# MOMO_2019.net
KiCad netlist of a schematic drawn in EAGLE
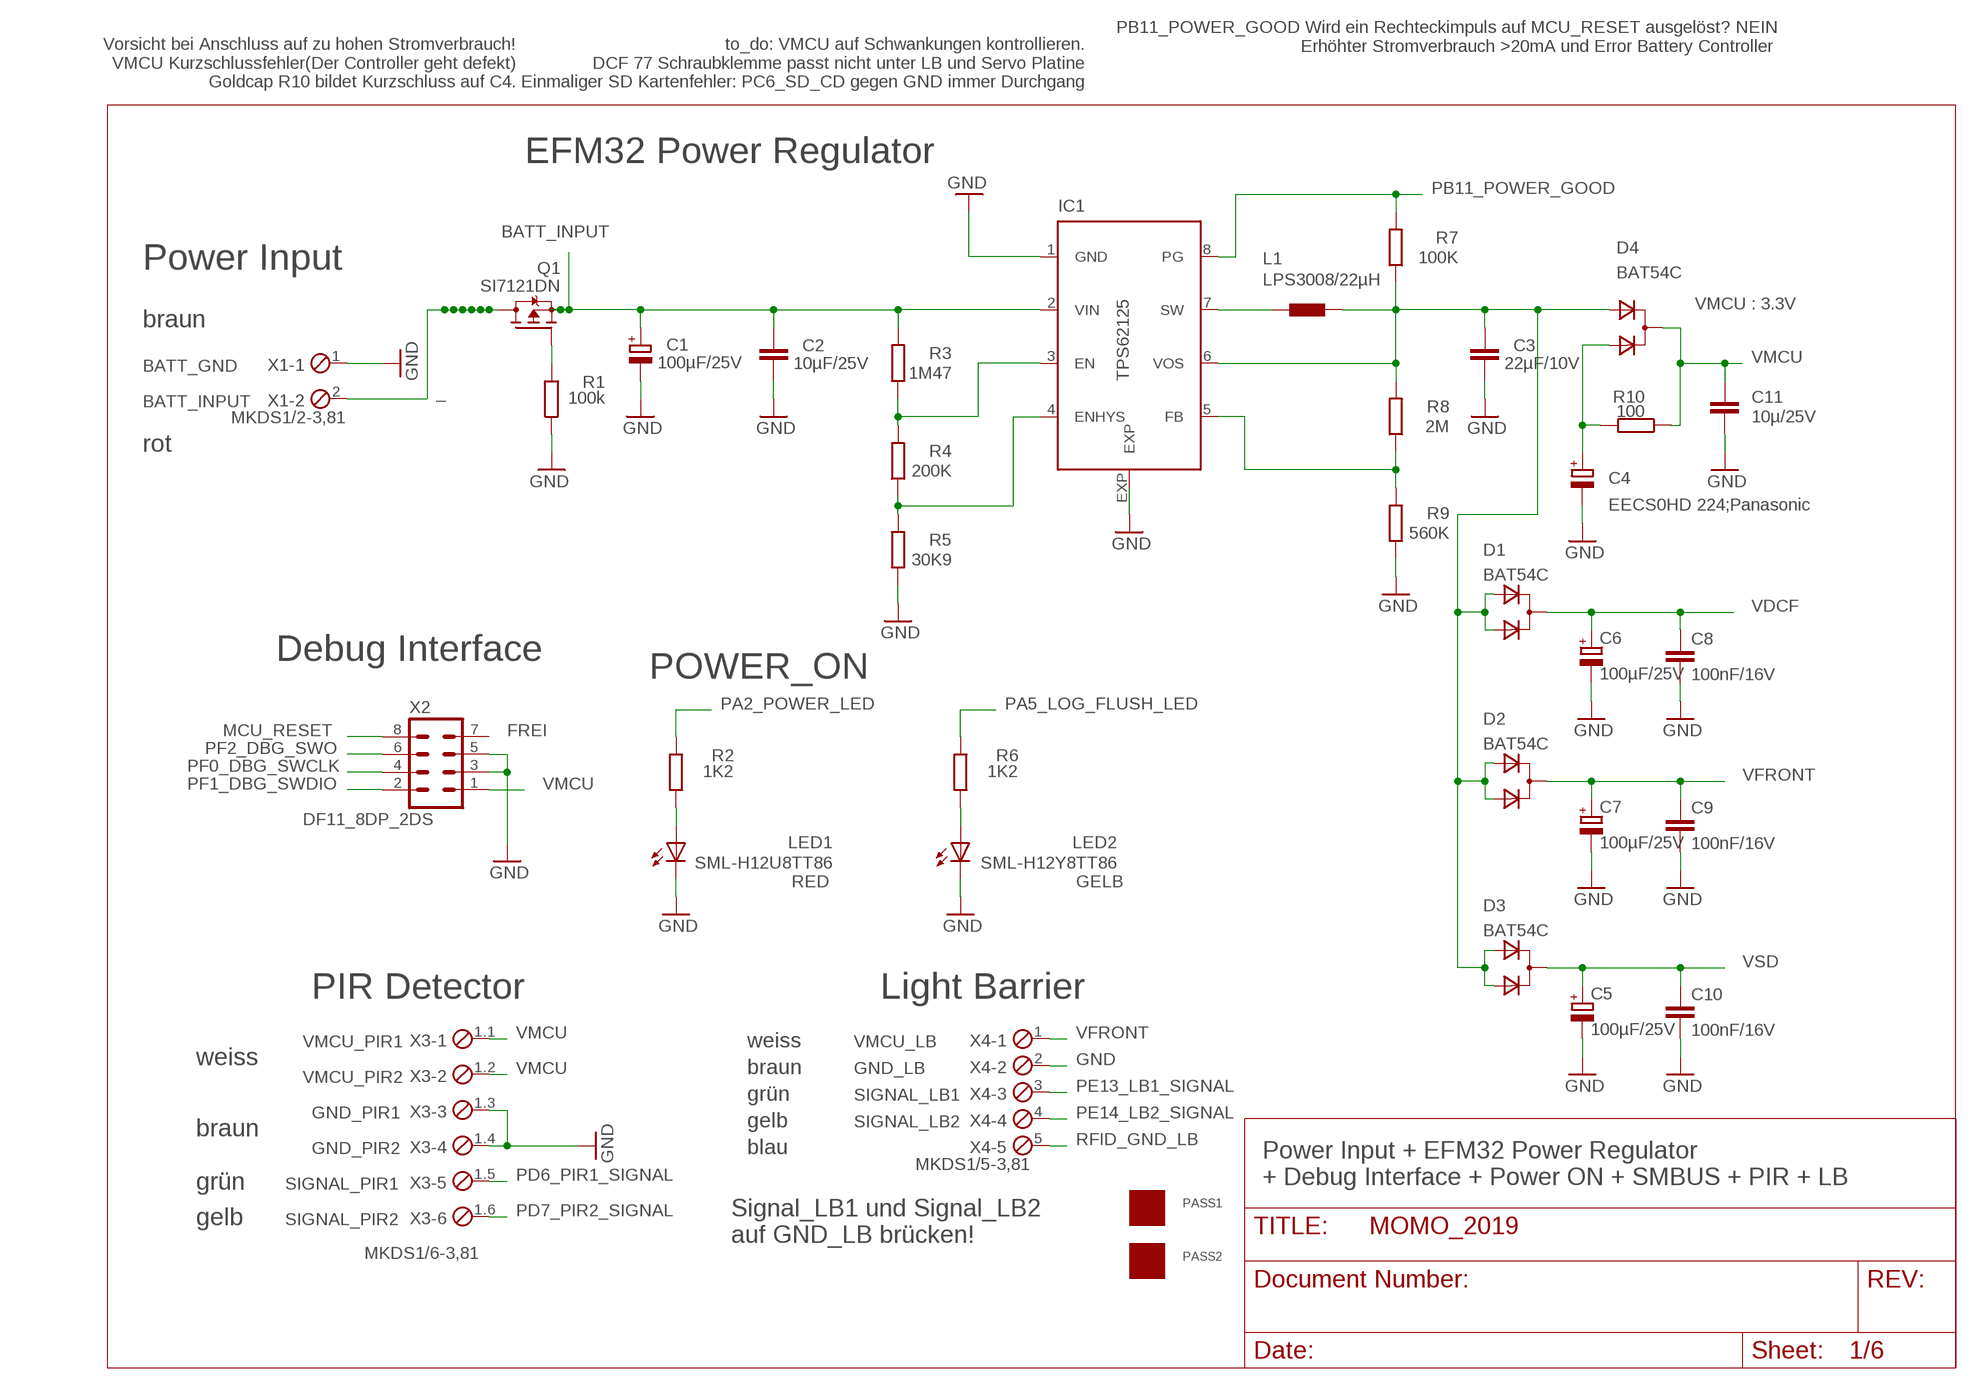
[diagram p0: schematic, sheet 1]
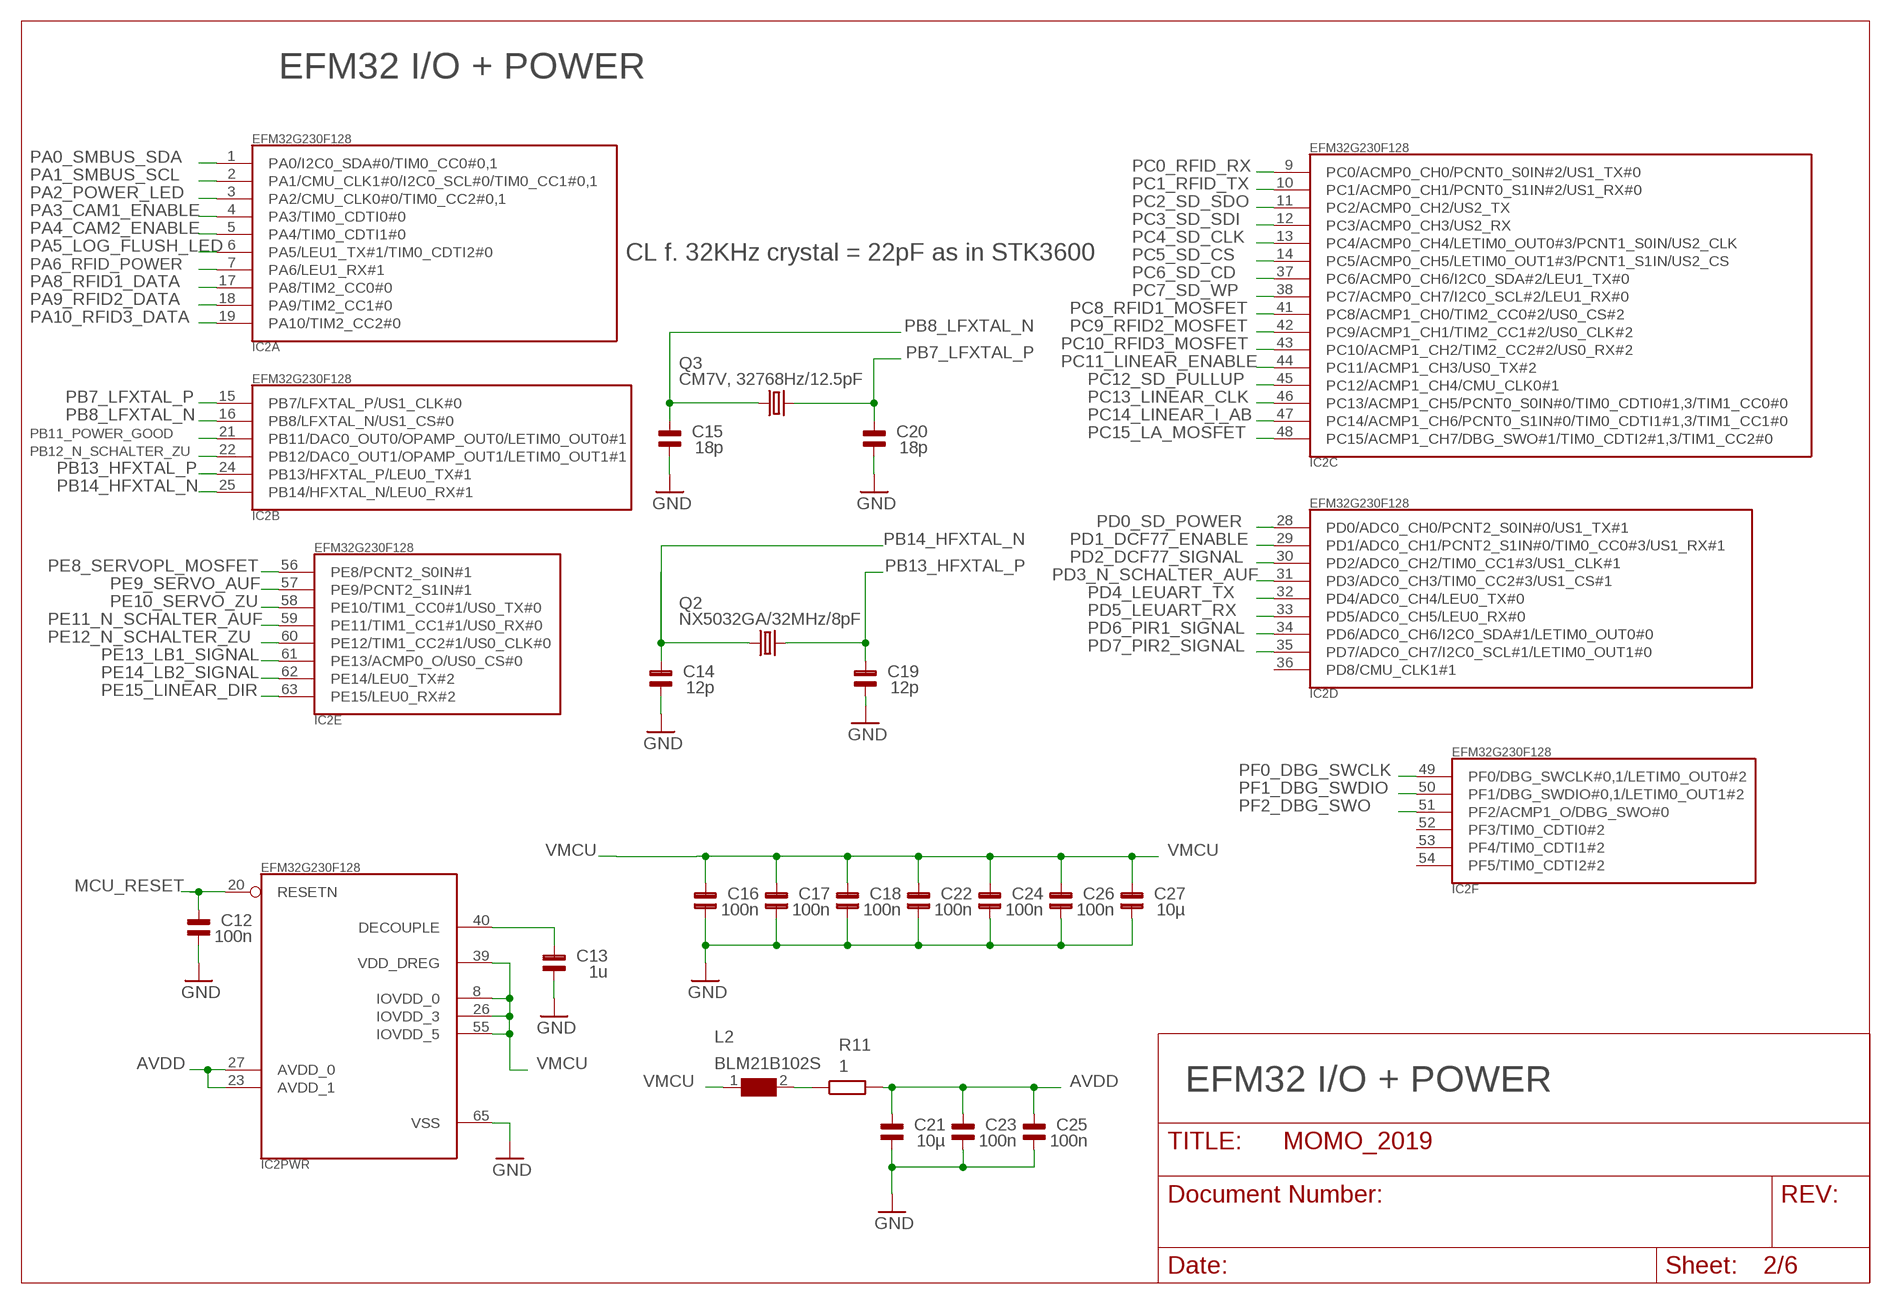
[diagram p1: schematic, sheet 2]
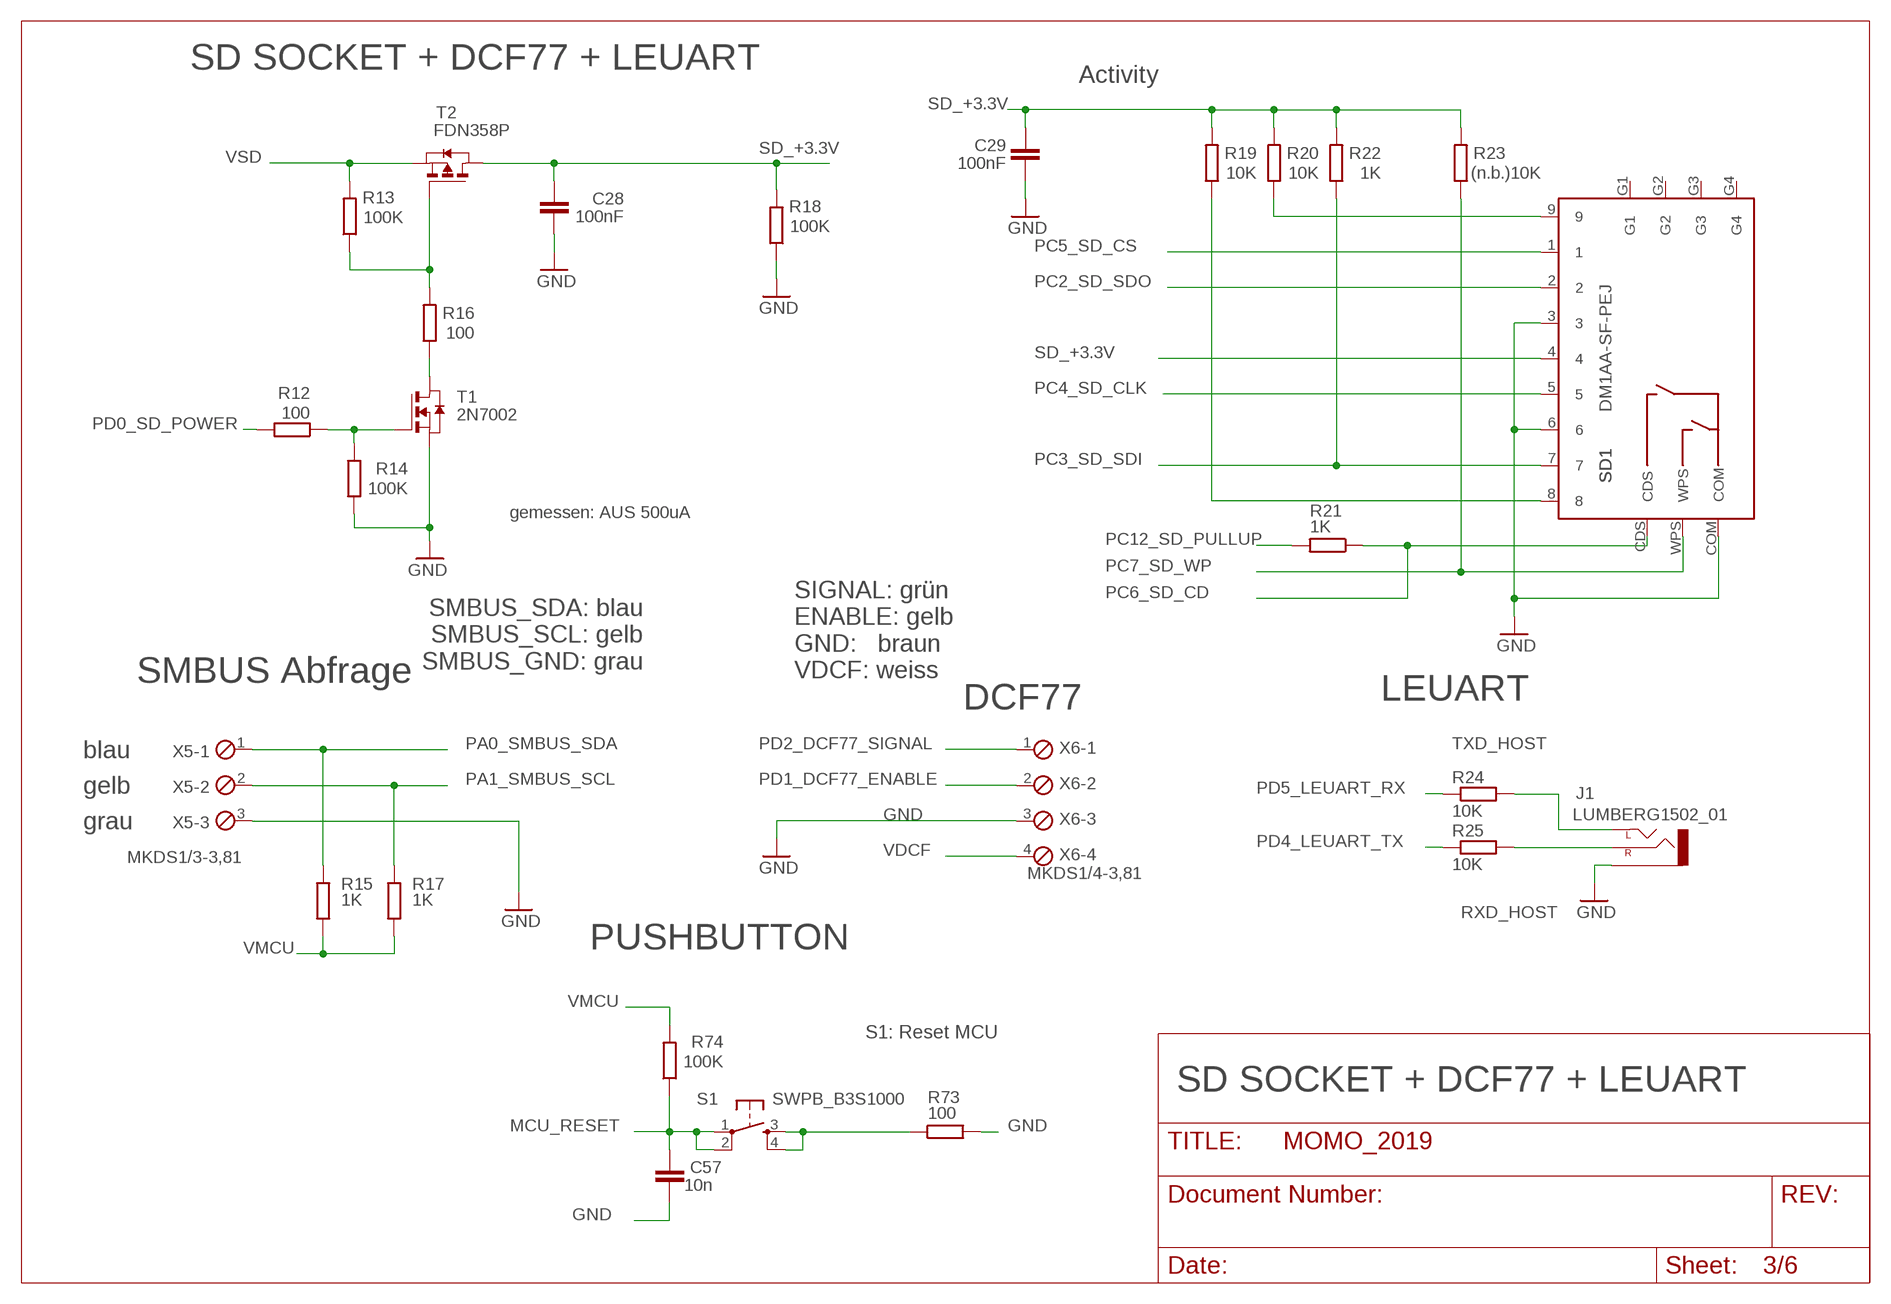
[diagram p2: schematic, sheet 3]
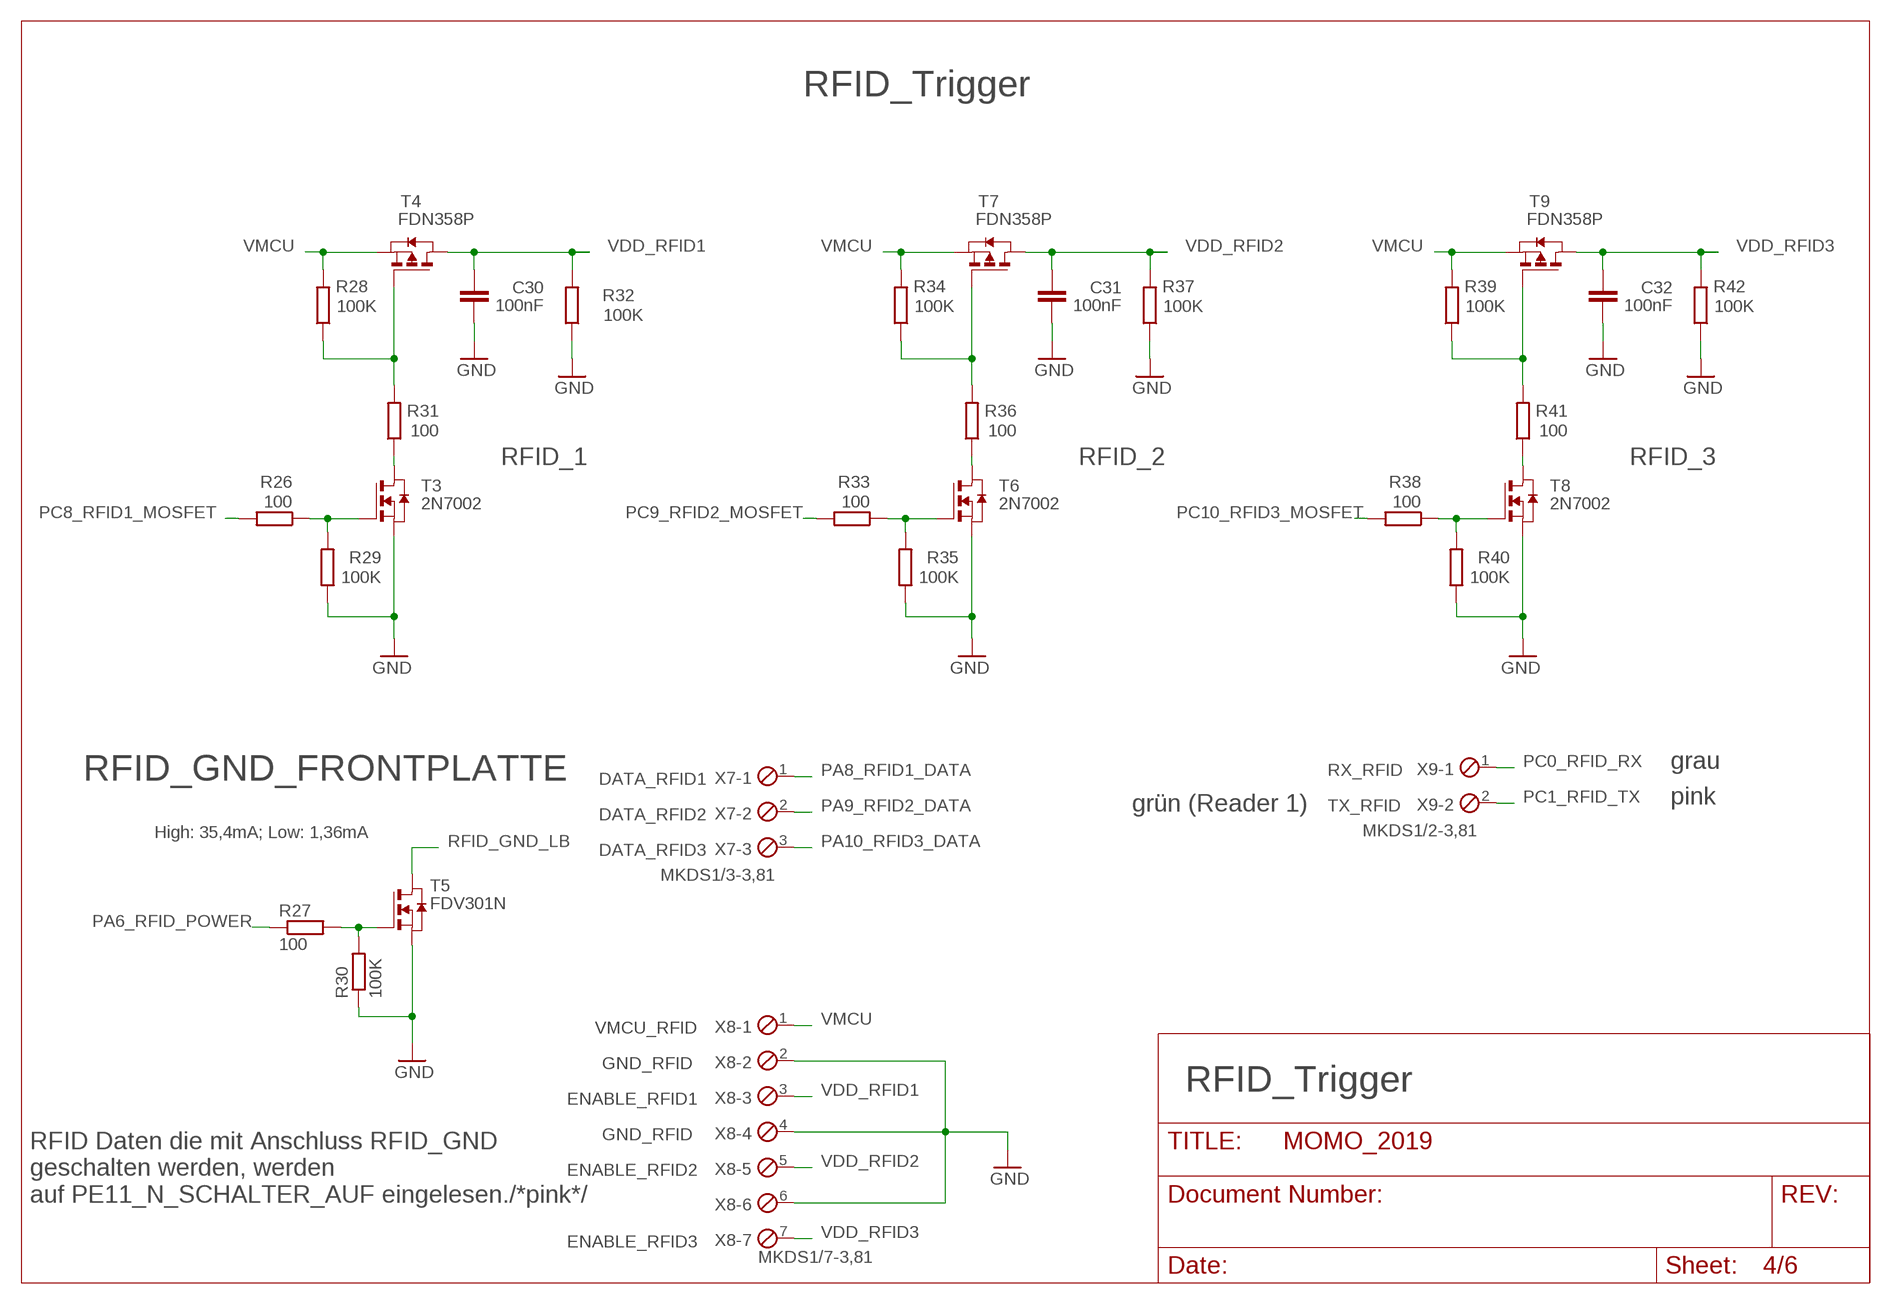
[diagram p3: schematic, sheet 4]
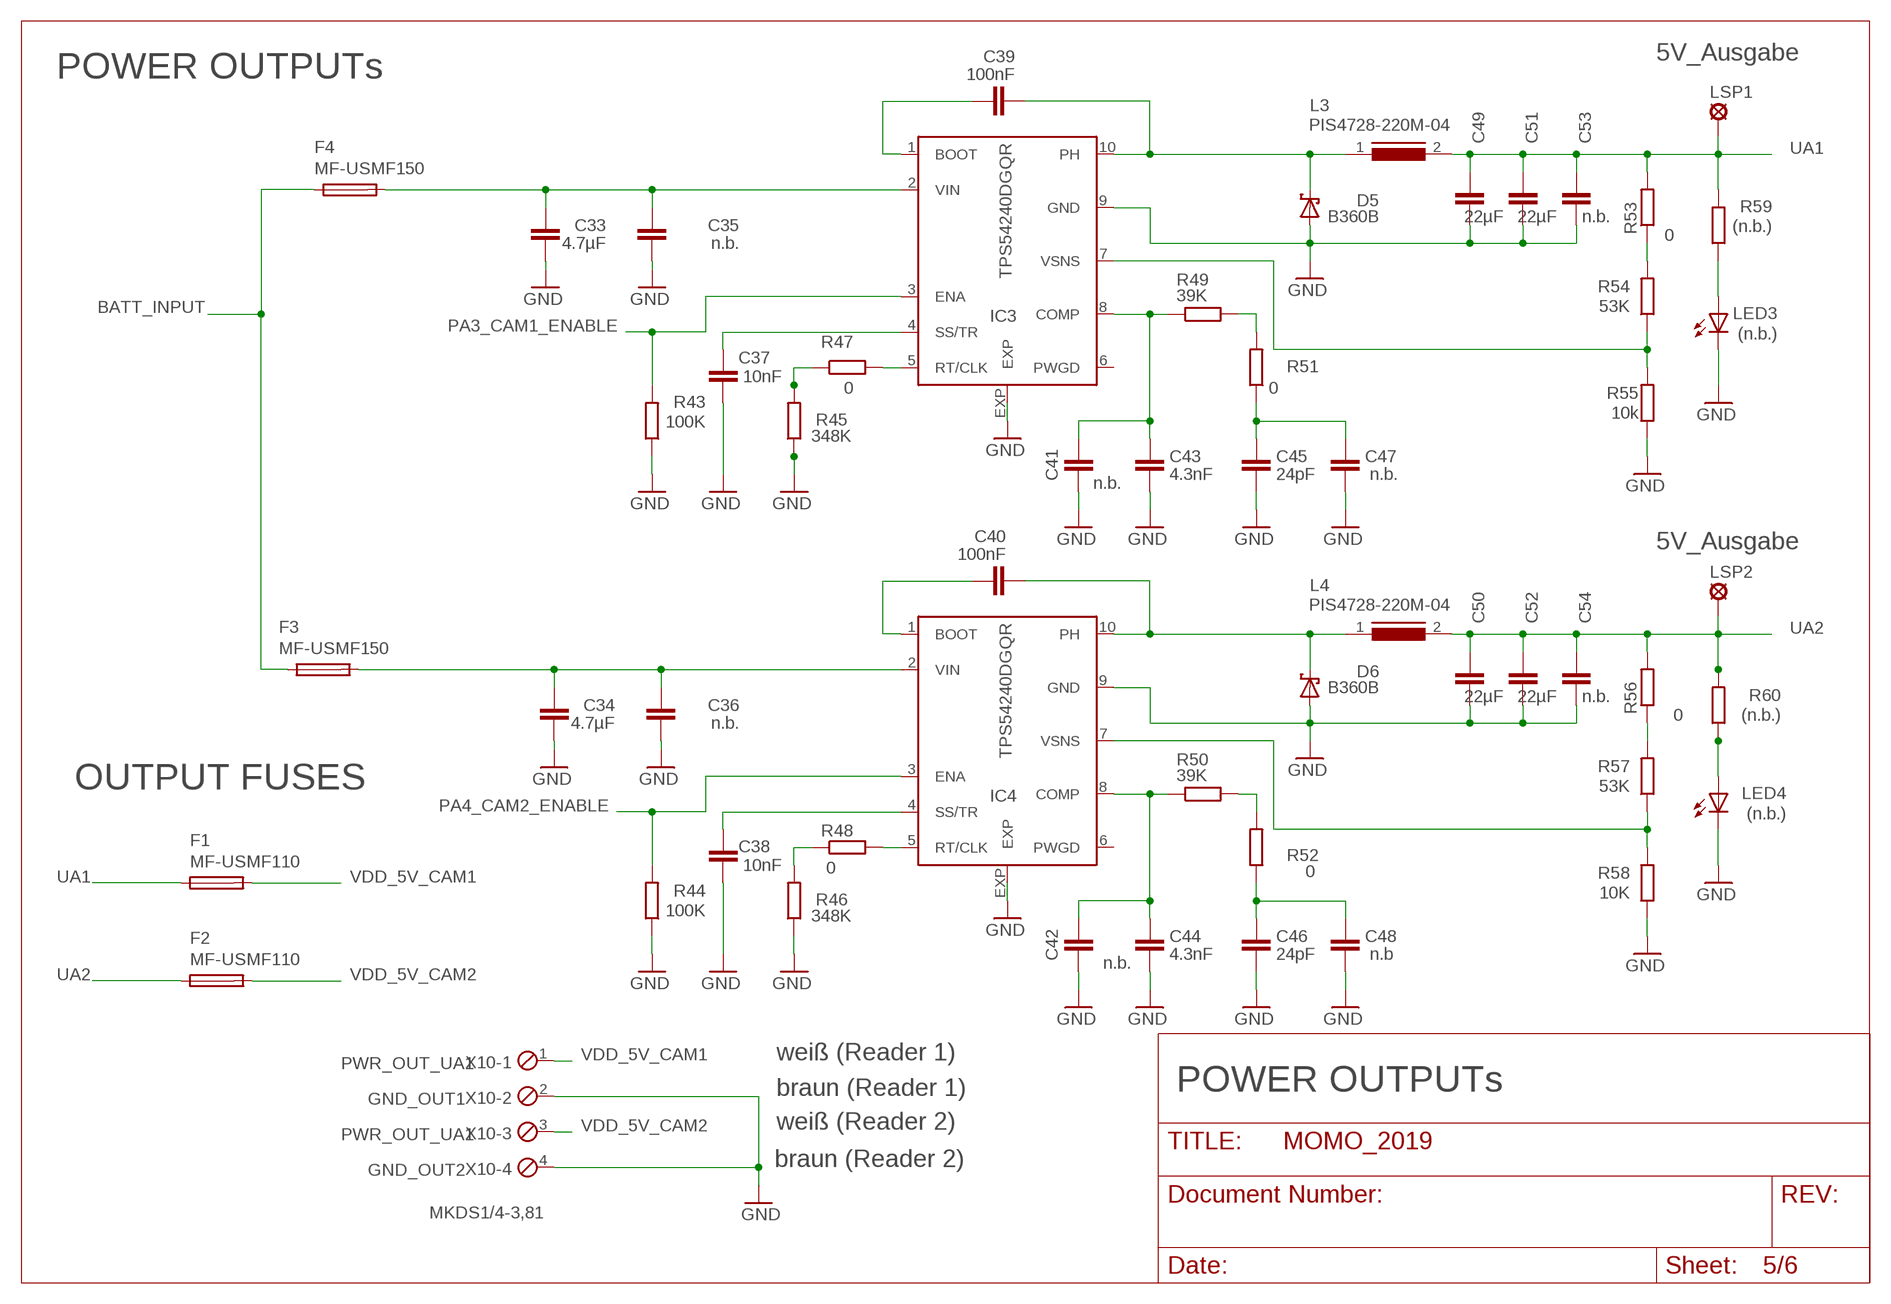
[diagram p4: schematic, sheet 5]
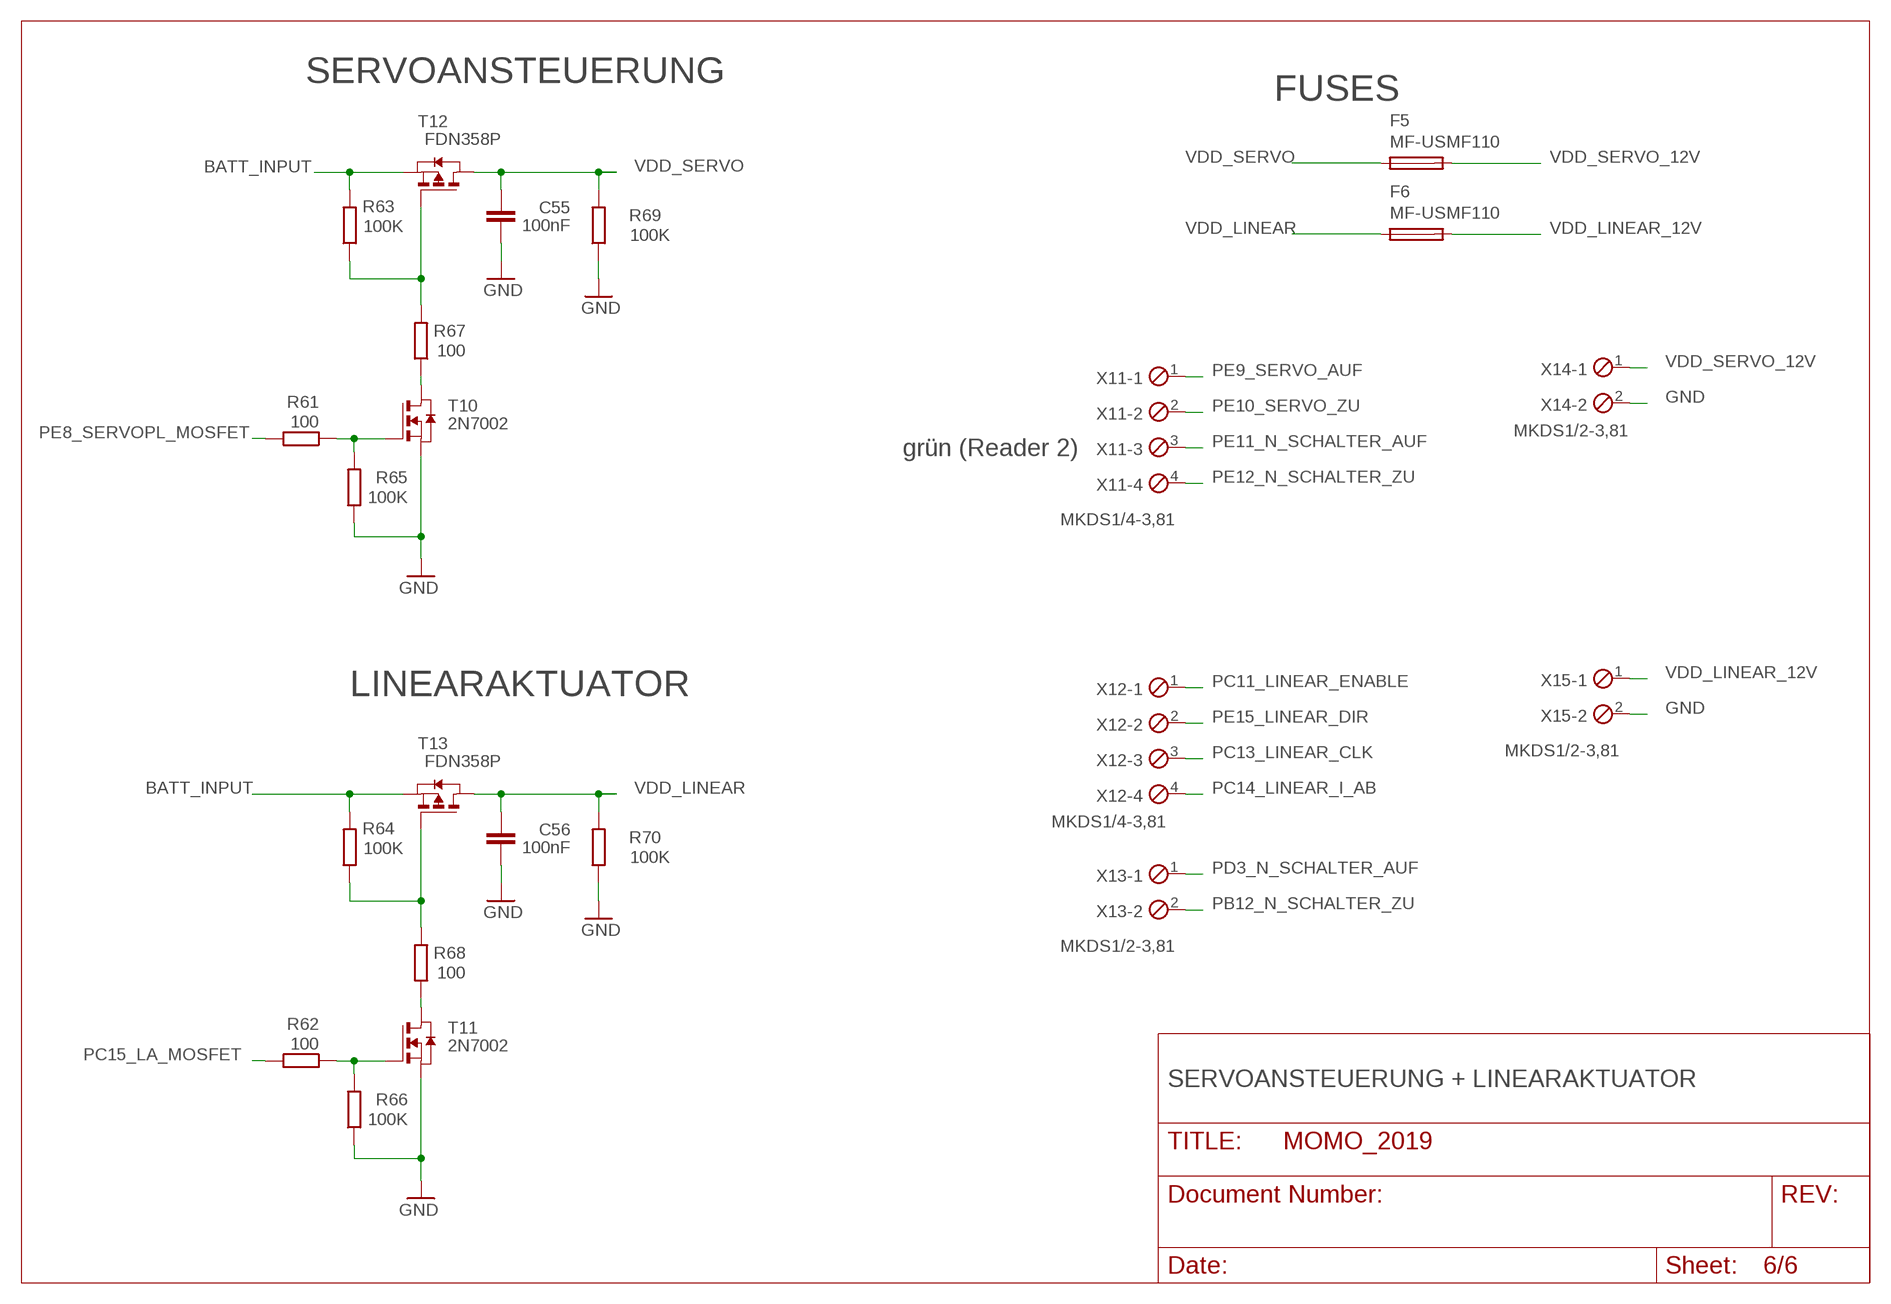
[diagram p5: schematic, sheet 6]

(export (version "E")
  (design (tool "Eeschema 10.0.6"))
  (components
    (comp (ref "C1")
      (value "100µF/25V")
      (footprint "eagle-import:PANASONIC_E")
      (libsource (lib "eagle-import") (part "CPOL-EUE"))
    )
    (comp (ref "C2")
      (value "10µF/25V")
      (footprint "eagle-import:C1206")
      (libsource (lib "eagle-import") (part "C-EUC1206"))
    )
    (comp (ref "C3")
      (value "22µF/10V")
      (footprint "eagle-import:C0603")
      (libsource (lib "eagle-import") (part "C-EUC0603"))
    )
    (comp (ref "C4")
      (value "EECS0HD 224;Panasonic")
      (footprint "eagle-import:GOLDCAPSPK-V")
      (libsource (lib "eagle-import") (part "GOLDCAPSPK-V"))
    )
    (comp (ref "C5")
      (value "100µF/25V")
      (footprint "eagle-import:PANASONIC_E")
      (libsource (lib "eagle-import") (part "CPOL-EUE"))
    )
    (comp (ref "C6")
      (value "100µF/25V")
      (footprint "eagle-import:PANASONIC_E")
      (libsource (lib "eagle-import") (part "CPOL-EUE"))
    )
    (comp (ref "C7")
      (value "100µF/25V")
      (footprint "eagle-import:PANASONIC_E")
      (libsource (lib "eagle-import") (part "CPOL-EUE"))
    )
    (comp (ref "C8")
      (value "100nF/16V")
      (footprint "eagle-import:C0805")
      (libsource (lib "eagle-import") (part "C-EUC0805"))
    )
    (comp (ref "C9")
      (value "100nF/16V")
      (footprint "eagle-import:C0805")
      (libsource (lib "eagle-import") (part "C-EUC0805"))
    )
    (comp (ref "C10")
      (value "100nF/16V")
      (footprint "eagle-import:C0805")
      (libsource (lib "eagle-import") (part "C-EUC0805"))
    )
    (comp (ref "C11")
      (value "10µ/25V")
      (footprint "eagle-import:C1206")
      (libsource (lib "eagle-import") (part "C-EUC1206"))
    )
    (comp (ref "D1")
      (value "BAT54C")
      (footprint "eagle-import:SOT-23$1")
      (libsource (lib "eagle-import") (part "D2A_SOT23"))
    )
    (comp (ref "D2")
      (value "BAT54C")
      (footprint "eagle-import:SOT-23$1")
      (libsource (lib "eagle-import") (part "D2A_SOT23"))
    )
    (comp (ref "D3")
      (value "BAT54C")
      (footprint "eagle-import:SOT-23$1")
      (libsource (lib "eagle-import") (part "D2A_SOT23"))
    )
    (comp (ref "D4")
      (value "BAT54C")
      (footprint "eagle-import:SOT-23$1")
      (libsource (lib "eagle-import") (part "D2A_SOT23"))
    )
    (comp (ref "IC1")
      (value "TPS62125")
      (footprint "eagle-import:DSG_PWSO-N8_EXP")
      (libsource (lib "eagle-import") (part "TPS62125"))
    )
    (comp (ref "L1")
      (value "LPS3008/22µH")
      (footprint "eagle-import:LPS3008")
      (libsource (lib "eagle-import") (part "LPS3008"))
    )
    (comp (ref "LED1")
      (value "SML-H12U8TT86")
      (footprint "eagle-import:CHIPLED_0805")
      (libsource (lib "eagle-import") (part "LEDCHIPLED_0805"))
    )
    (comp (ref "LED2")
      (value "SML-H12Y8TT86")
      (footprint "eagle-import:CHIPLED_0805")
      (libsource (lib "eagle-import") (part "LEDCHIPLED_0805"))
    )
    (comp (ref "PASS1")
      (value "ROUND_1MM1.5")
      (footprint "eagle-import:ROUND2_1.5MM")
      (libsource (lib "eagle-import") (part "ROUND_1MM1.5"))
    )
    (comp (ref "PASS2")
      (value "ROUND_1MM1.5")
      (footprint "eagle-import:ROUND2_1.5MM")
      (libsource (lib "eagle-import") (part "ROUND_1MM1.5"))
    )
    (comp (ref "Q1")
      (value "SI7121DN")
      (footprint "eagle-import:TRANSISTOR-FET_1212-8S")
      (libsource (lib "eagle-import") (part "TRANSISTOR-FET_SI7113DN"))
    )
    (comp (ref "R1")
      (value "100k")
      (footprint "eagle-import:R0805")
      (libsource (lib "eagle-import") (part "resistor_R-EU_R0805"))
    )
    (comp (ref "R2")
      (value "1K2")
      (footprint "eagle-import:R0805")
      (libsource (lib "eagle-import") (part "resistor_R-EU_R0805"))
    )
    (comp (ref "R3")
      (value "1M47")
      (footprint "eagle-import:R0805")
      (libsource (lib "eagle-import") (part "R-EU_R0805"))
    )
    (comp (ref "R4")
      (value "200K")
      (footprint "eagle-import:R0805")
      (libsource (lib "eagle-import") (part "R-EU_R0805"))
    )
    (comp (ref "R5")
      (value "30K9")
      (footprint "eagle-import:R0805")
      (libsource (lib "eagle-import") (part "R-EU_R0805"))
    )
    (comp (ref "R6")
      (value "1K2")
      (footprint "eagle-import:R0805")
      (libsource (lib "eagle-import") (part "resistor_R-EU_R0805"))
    )
    (comp (ref "R7")
      (value "100K")
      (footprint "eagle-import:R0805")
      (libsource (lib "eagle-import") (part "R-EU_R0805"))
    )
    (comp (ref "R8")
      (value "2M")
      (footprint "eagle-import:R0805")
      (libsource (lib "eagle-import") (part "R-EU_R0805"))
    )
    (comp (ref "R9")
      (value "560K")
      (footprint "eagle-import:R0805")
      (libsource (lib "eagle-import") (part "R-EU_R0805"))
    )
    (comp (ref "R10")
      (value "100")
      (footprint "eagle-import:R0805")
      (libsource (lib "eagle-import") (part "R-EU_R0805"))
    )
    (comp (ref "X1")
      (value "MKDS1/2-3,81")
      (footprint "eagle-import:2POL381")
      (libsource (lib "eagle-import") (part "MKDS1/2-3,81"))
    )
    (comp (ref "X2")
      (value "DF11_8DP_2DS")
      (footprint "eagle-import:DP11_8DP-2DS")
      (libsource (lib "eagle-import") (part "DP11_8DP_2DS"))
    )
    (comp (ref "X3")
      (value "MKDS1/6-3,81")
      (footprint "eagle-import:6POL381")
      (libsource (lib "eagle-import") (part "MKDS1/6-3,81"))
    )
    (comp (ref "X4")
      (value "MKDS1/5-3,81")
      (footprint "eagle-import:5POL381")
      (libsource (lib "eagle-import") (part "MKDS1/5-3,81"))
    )
    (comp (ref "C28")
      (value "100nF")
      (footprint "eagle-import:C0603")
      (libsource (lib "eagle-import") (part "resistor_C-EUC0603"))
    )
    (comp (ref "C29")
      (value "100nF")
      (footprint "eagle-import:C0603")
      (libsource (lib "eagle-import") (part "resistor_C-EUC0603"))
    )
    (comp (ref "C57")
      (value "10n")
      (footprint "eagle-import:C0603")
      (libsource (lib "eagle-import") (part "resistor_C-EUC0603"))
    )
    (comp (ref "J1")
      (value "LUMBERG1502_01")
      (footprint "eagle-import:LUMBERG1502_01")
      (libsource (lib "eagle-import") (part "LUMBERG1502_01"))
    )
    (comp (ref "R12")
      (value "100")
      (footprint "eagle-import:R0805")
      (libsource (lib "eagle-import") (part "resistor_R-EU_R0805"))
    )
    (comp (ref "R13")
      (value "100K")
      (footprint "eagle-import:R0805")
      (libsource (lib "eagle-import") (part "resistor_R-EU_R0805"))
    )
    (comp (ref "R14")
      (value "100K")
      (footprint "eagle-import:R0805")
      (libsource (lib "eagle-import") (part "resistor_R-EU_R0805"))
    )
    (comp (ref "R15")
      (value "1K")
      (footprint "eagle-import:R0805")
      (libsource (lib "eagle-import") (part "resistor_R-EU_R0805"))
    )
    (comp (ref "R16")
      (value "100")
      (footprint "eagle-import:R0805")
      (libsource (lib "eagle-import") (part "resistor_R-EU_R0805"))
    )
    (comp (ref "R17")
      (value "1K")
      (footprint "eagle-import:R0805")
      (libsource (lib "eagle-import") (part "resistor_R-EU_R0805"))
    )
    (comp (ref "R18")
      (value "100K")
      (footprint "eagle-import:R0805")
      (libsource (lib "eagle-import") (part "resistor_R-EU_R0805"))
    )
    (comp (ref "R19")
      (value "10K")
      (footprint "eagle-import:R0805")
      (libsource (lib "eagle-import") (part "resistor_R-EU_R0805"))
    )
    (comp (ref "R20")
      (value "10K")
      (footprint "eagle-import:R0805")
      (libsource (lib "eagle-import") (part "resistor_R-EU_R0805"))
    )
    (comp (ref "R21")
      (value "1K")
      (footprint "eagle-import:R0805")
      (libsource (lib "eagle-import") (part "resistor_R-EU_R0805"))
    )
    (comp (ref "R22")
      (value "1K")
      (footprint "eagle-import:R0805")
      (libsource (lib "eagle-import") (part "resistor_R-EU_R0805"))
    )
    (comp (ref "R23")
      (value "(n.b.)10K")
      (footprint "eagle-import:R0805")
      (libsource (lib "eagle-import") (part "resistor_R-EU_R0805"))
    )
    (comp (ref "R24")
      (value "10K")
      (footprint "eagle-import:R0805")
      (libsource (lib "eagle-import") (part "R-EU_R0805"))
    )
    (comp (ref "R25")
      (value "10K")
      (footprint "eagle-import:R0805")
      (libsource (lib "eagle-import") (part "R-EU_R0805"))
    )
    (comp (ref "R73")
      (value "100")
      (footprint "eagle-import:R0805")
      (libsource (lib "eagle-import") (part "resistor_R-EU_R0805"))
    )
    (comp (ref "R74")
      (value "100K")
      (footprint "eagle-import:R0805")
      (libsource (lib "eagle-import") (part "resistor_R-EU_R0805"))
    )
    (comp (ref "S1")
      (value "SWPB_B3S1000")
      (footprint "eagle-import:DTSM-6")
      (libsource (lib "eagle-import") (part "DTSM-6"))
    )
    (comp (ref "SD1")
      (value "DM1AA-SF-PEJ")
      (footprint "eagle-import:DM1AA-SF-PEJ")
      (libsource (lib "eagle-import") (part "DM1AA-SF-PEJ"))
    )
    (comp (ref "T1")
      (value "2N7002")
      (footprint "eagle-import:ZETEX_SOT-23")
      (libsource (lib "eagle-import") (part "ZETEX_NMOSSOT23"))
    )
    (comp (ref "T2")
      (value "FDN358P")
      (footprint "eagle-import:ZETEX_SOT-23")
      (libsource (lib "eagle-import") (part "ZETEX_PMOSSOT23"))
    )
    (comp (ref "X5")
      (value "MKDS1/3-3,81")
      (footprint "eagle-import:3POL381")
      (libsource (lib "eagle-import") (part "MKDS1/3-3,81"))
    )
    (comp (ref "X6")
      (value "MKDS1/4-3,81")
      (footprint "eagle-import:4POL381")
      (libsource (lib "eagle-import") (part "MKDS1/4-3,81"))
    )
    (comp (ref "C30")
      (value "100nF")
      (footprint "eagle-import:C0603")
      (libsource (lib "eagle-import") (part "resistor_C-EUC0603"))
    )
    (comp (ref "C31")
      (value "100nF")
      (footprint "eagle-import:C0603")
      (libsource (lib "eagle-import") (part "resistor_C-EUC0603"))
    )
    (comp (ref "C32")
      (value "100nF")
      (footprint "eagle-import:C0603")
      (libsource (lib "eagle-import") (part "resistor_C-EUC0603"))
    )
    (comp (ref "R26")
      (value "100")
      (footprint "eagle-import:R0805")
      (libsource (lib "eagle-import") (part "resistor_R-EU_R0805"))
    )
    (comp (ref "R27")
      (value "100")
      (footprint "eagle-import:R0805")
      (libsource (lib "eagle-import") (part "R-EU_R0805"))
    )
    (comp (ref "R28")
      (value "100K")
      (footprint "eagle-import:R0805")
      (libsource (lib "eagle-import") (part "resistor_R-EU_R0805"))
    )
    (comp (ref "R29")
      (value "100K")
      (footprint "eagle-import:R0805")
      (libsource (lib "eagle-import") (part "resistor_R-EU_R0805"))
    )
    (comp (ref "R30")
      (value "100K")
      (footprint "eagle-import:R0805")
      (libsource (lib "eagle-import") (part "R-EU_R0805"))
    )
    (comp (ref "R31")
      (value "100")
      (footprint "eagle-import:R0805")
      (libsource (lib "eagle-import") (part "resistor_R-EU_R0805"))
    )
    (comp (ref "R32")
      (value "100K")
      (footprint "eagle-import:R0805")
      (libsource (lib "eagle-import") (part "resistor_R-EU_R0805"))
    )
    (comp (ref "R33")
      (value "100")
      (footprint "eagle-import:R0805")
      (libsource (lib "eagle-import") (part "resistor_R-EU_R0805"))
    )
    (comp (ref "R34")
      (value "100K")
      (footprint "eagle-import:R0805")
      (libsource (lib "eagle-import") (part "resistor_R-EU_R0805"))
    )
    (comp (ref "R35")
      (value "100K")
      (footprint "eagle-import:R0805")
      (libsource (lib "eagle-import") (part "resistor_R-EU_R0805"))
    )
    (comp (ref "R36")
      (value "100")
      (footprint "eagle-import:R0805")
      (libsource (lib "eagle-import") (part "resistor_R-EU_R0805"))
    )
    (comp (ref "R37")
      (value "100K")
      (footprint "eagle-import:R0805")
      (libsource (lib "eagle-import") (part "resistor_R-EU_R0805"))
    )
    (comp (ref "R38")
      (value "100")
      (footprint "eagle-import:R0805")
      (libsource (lib "eagle-import") (part "resistor_R-EU_R0805"))
    )
    (comp (ref "R39")
      (value "100K")
      (footprint "eagle-import:R0805")
      (libsource (lib "eagle-import") (part "resistor_R-EU_R0805"))
    )
    (comp (ref "R40")
      (value "100K")
      (footprint "eagle-import:R0805")
      (libsource (lib "eagle-import") (part "resistor_R-EU_R0805"))
    )
    (comp (ref "R41")
      (value "100")
      (footprint "eagle-import:R0805")
      (libsource (lib "eagle-import") (part "resistor_R-EU_R0805"))
    )
    (comp (ref "R42")
      (value "100K")
      (footprint "eagle-import:R0805")
      (libsource (lib "eagle-import") (part "resistor_R-EU_R0805"))
    )
    (comp (ref "T3")
      (value "2N7002")
      (footprint "eagle-import:ZETEX_SOT-23")
      (libsource (lib "eagle-import") (part "ZETEX_NMOSSOT23"))
    )
    (comp (ref "T4")
      (value "FDN358P")
      (footprint "eagle-import:ZETEX_SOT-23")
      (libsource (lib "eagle-import") (part "ZETEX_PMOSSOT23"))
    )
    (comp (ref "T5")
      (value "FDV301N")
      (footprint "eagle-import:SOT-23")
      (fields (field (name "OC_FARNELL") "unknown") (field (name "OC_NEWARK") "unknown"))
      (libsource (lib "eagle-import") (part "NMOSSOT23"))
    )
    (comp (ref "T6")
      (value "2N7002")
      (footprint "eagle-import:ZETEX_SOT-23")
      (libsource (lib "eagle-import") (part "ZETEX_NMOSSOT23"))
    )
    (comp (ref "T7")
      (value "FDN358P")
      (footprint "eagle-import:ZETEX_SOT-23")
      (libsource (lib "eagle-import") (part "ZETEX_PMOSSOT23"))
    )
    (comp (ref "T8")
      (value "2N7002")
      (footprint "eagle-import:ZETEX_SOT-23")
      (libsource (lib "eagle-import") (part "ZETEX_NMOSSOT23"))
    )
    (comp (ref "T9")
      (value "FDN358P")
      (footprint "eagle-import:ZETEX_SOT-23")
      (libsource (lib "eagle-import") (part "ZETEX_PMOSSOT23"))
    )
    (comp (ref "X7")
      (value "MKDS1/3-3,81")
      (footprint "eagle-import:3POL381")
      (libsource (lib "eagle-import") (part "MKDS1/3-3,81"))
    )
    (comp (ref "X8")
      (value "MKDS1/7-3,81")
      (footprint "eagle-import:7POL381")
      (libsource (lib "eagle-import") (part "MKDS1/7-3,81"))
    )
    (comp (ref "X9")
      (value "MKDS1/2-3,81")
      (footprint "eagle-import:2POL381")
      (libsource (lib "eagle-import") (part "MKDS1/2-3,81"))
    )
    (comp (ref "C55")
      (value "100nF")
      (footprint "eagle-import:C0603")
      (libsource (lib "eagle-import") (part "resistor_C-EUC0603"))
    )
    (comp (ref "C56")
      (value "100nF")
      (footprint "eagle-import:C0603")
      (libsource (lib "eagle-import") (part "resistor_C-EUC0603"))
    )
    (comp (ref "F5")
      (value "MF-USMF110")
      (footprint "eagle-import:PFUF_1210POLY")
      (libsource (lib "eagle-import") (part "PFUF"))
    )
    (comp (ref "F6")
      (value "MF-USMF110")
      (footprint "eagle-import:PFUF_1210POLY")
      (libsource (lib "eagle-import") (part "PFUF"))
    )
    (comp (ref "R61")
      (value "100")
      (footprint "eagle-import:R0805")
      (libsource (lib "eagle-import") (part "resistor_R-EU_R0805"))
    )
    (comp (ref "R62")
      (value "100")
      (footprint "eagle-import:R0805")
      (libsource (lib "eagle-import") (part "resistor_R-EU_R0805"))
    )
    (comp (ref "R63")
      (value "100K")
      (footprint "eagle-import:R0805")
      (libsource (lib "eagle-import") (part "resistor_R-EU_R0805"))
    )
    (comp (ref "R64")
      (value "100K")
      (footprint "eagle-import:R0805")
      (libsource (lib "eagle-import") (part "resistor_R-EU_R0805"))
    )
    (comp (ref "R65")
      (value "100K")
      (footprint "eagle-import:R0805")
      (libsource (lib "eagle-import") (part "resistor_R-EU_R0805"))
    )
    (comp (ref "R66")
      (value "100K")
      (footprint "eagle-import:R0805")
      (libsource (lib "eagle-import") (part "resistor_R-EU_R0805"))
    )
    (comp (ref "R67")
      (value "100")
      (footprint "eagle-import:R0805")
      (libsource (lib "eagle-import") (part "resistor_R-EU_R0805"))
    )
    (comp (ref "R68")
      (value "100")
      (footprint "eagle-import:R0805")
      (libsource (lib "eagle-import") (part "resistor_R-EU_R0805"))
    )
    (comp (ref "R69")
      (value "100K")
      (footprint "eagle-import:R0805")
      (libsource (lib "eagle-import") (part "resistor_R-EU_R0805"))
    )
    (comp (ref "R70")
      (value "100K")
      (footprint "eagle-import:R0805")
      (libsource (lib "eagle-import") (part "resistor_R-EU_R0805"))
    )
    (comp (ref "T10")
      (value "2N7002")
      (footprint "eagle-import:ZETEX_SOT-23")
      (libsource (lib "eagle-import") (part "ZETEX_NMOSSOT23"))
    )
    (comp (ref "T11")
      (value "2N7002")
      (footprint "eagle-import:ZETEX_SOT-23")
      (libsource (lib "eagle-import") (part "ZETEX_NMOSSOT23"))
    )
    (comp (ref "T12")
      (value "FDN358P")
      (footprint "eagle-import:ZETEX_SOT-23")
      (libsource (lib "eagle-import") (part "ZETEX_PMOSSOT23"))
    )
    (comp (ref "T13")
      (value "FDN358P")
      (footprint "eagle-import:ZETEX_SOT-23")
      (libsource (lib "eagle-import") (part "ZETEX_PMOSSOT23"))
    )
    (comp (ref "X11")
      (value "MKDS1/4-3,81")
      (footprint "eagle-import:4POL381")
      (libsource (lib "eagle-import") (part "MKDS1/4-3,81"))
    )
    (comp (ref "X12")
      (value "MKDS1/4-3,81")
      (footprint "eagle-import:4POL381")
      (libsource (lib "eagle-import") (part "MKDS1/4-3,81"))
    )
    (comp (ref "X13")
      (value "MKDS1/2-3,81")
      (footprint "eagle-import:2POL381")
      (libsource (lib "eagle-import") (part "MKDS1/2-3,81"))
    )
    (comp (ref "X14")
      (value "MKDS1/2-3,81")
      (footprint "eagle-import:2POL381")
      (libsource (lib "eagle-import") (part "MKDS1/2-3,81"))
    )
    (comp (ref "X15")
      (value "MKDS1/2-3,81")
      (footprint "eagle-import:2POL381")
      (libsource (lib "eagle-import") (part "MKDS1/2-3,81"))
    )
    (comp (ref "C33")
      (value "4.7µF")
      (footprint "eagle-import:C1210")
      (libsource (lib "eagle-import") (part "C-EUC1210"))
    )
    (comp (ref "C34")
      (value "4.7µF")
      (footprint "eagle-import:C1210")
      (libsource (lib "eagle-import") (part "C-EUC1210"))
    )
    (comp (ref "C35")
      (value "n.b.")
      (footprint "eagle-import:C1210")
      (libsource (lib "eagle-import") (part "C-EUC1210"))
    )
    (comp (ref "C36")
      (value "n.b.")
      (footprint "eagle-import:C1210")
      (libsource (lib "eagle-import") (part "C-EUC1210"))
    )
    (comp (ref "C37")
      (value "10nF")
      (footprint "eagle-import:C0603")
      (libsource (lib "eagle-import") (part "C-EUC0603"))
    )
    (comp (ref "C38")
      (value "10nF")
      (footprint "eagle-import:C0603")
      (libsource (lib "eagle-import") (part "C-EUC0603"))
    )
    (comp (ref "C39")
      (value "100nF")
      (footprint "eagle-import:C0603")
      (libsource (lib "eagle-import") (part "C-EUC0603"))
    )
    (comp (ref "C40")
      (value "100nF")
      (footprint "eagle-import:C0603")
      (libsource (lib "eagle-import") (part "C-EUC0603"))
    )
    (comp (ref "C41")
      (value "n.b.")
      (footprint "eagle-import:C0603")
      (libsource (lib "eagle-import") (part "C-EUC0603"))
    )
    (comp (ref "C42")
      (value "n.b.")
      (footprint "eagle-import:C0603")
      (libsource (lib "eagle-import") (part "C-EUC0603"))
    )
    (comp (ref "C43")
      (value "4.3nF")
      (footprint "eagle-import:C0603")
      (libsource (lib "eagle-import") (part "C-EUC0603"))
    )
    (comp (ref "C44")
      (value "4.3nF")
      (footprint "eagle-import:C0603")
      (libsource (lib "eagle-import") (part "C-EUC0603"))
    )
    (comp (ref "C45")
      (value "24pF")
      (footprint "eagle-import:C0603")
      (libsource (lib "eagle-import") (part "C-EUC0603"))
    )
    (comp (ref "C46")
      (value "24pF")
      (footprint "eagle-import:C0603")
      (libsource (lib "eagle-import") (part "C-EUC0603"))
    )
    (comp (ref "C47")
      (value "n.b.")
      (footprint "eagle-import:C0603")
      (libsource (lib "eagle-import") (part "C-EUC0603"))
    )
    (comp (ref "C48")
      (value "n.b")
      (footprint "eagle-import:C0603")
      (libsource (lib "eagle-import") (part "C-EUC0603"))
    )
    (comp (ref "C49")
      (value "22µF")
      (footprint "eagle-import:C1210")
      (libsource (lib "eagle-import") (part "C-EUC1210"))
    )
    (comp (ref "C50")
      (value "22µF")
      (footprint "eagle-import:C1210")
      (libsource (lib "eagle-import") (part "C-EUC1210"))
    )
    (comp (ref "C51")
      (value "22µF")
      (footprint "eagle-import:C1210")
      (libsource (lib "eagle-import") (part "C-EUC1210"))
    )
    (comp (ref "C52")
      (value "22µF")
      (footprint "eagle-import:C1210")
      (libsource (lib "eagle-import") (part "C-EUC1210"))
    )
    (comp (ref "C53")
      (value "n.b.")
      (footprint "eagle-import:C1210")
      (libsource (lib "eagle-import") (part "C-EUC1210"))
    )
    (comp (ref "C54")
      (value "n.b.")
      (footprint "eagle-import:C1210")
      (libsource (lib "eagle-import") (part "C-EUC1210"))
    )
    (comp (ref "D5")
      (value "B360B")
      (footprint "eagle-import:SMB")
      (libsource (lib "eagle-import") (part "SCHOTTKY-DIODESMD"))
    )
    (comp (ref "D6")
      (value "B360B")
      (footprint "eagle-import:SMB")
      (libsource (lib "eagle-import") (part "SCHOTTKY-DIODESMD"))
    )
    (comp (ref "F1")
      (value "MF-USMF110")
      (footprint "eagle-import:PFUF_1210POLY")
      (libsource (lib "eagle-import") (part "PFUF"))
    )
    (comp (ref "F2")
      (value "MF-USMF110")
      (footprint "eagle-import:PFUF_1210POLY")
      (libsource (lib "eagle-import") (part "PFUF"))
    )
    (comp (ref "F3")
      (value "MF-USMF150")
      (footprint "eagle-import:PFUF_1210POLY")
      (libsource (lib "eagle-import") (part "PFUF"))
    )
    (comp (ref "F4")
      (value "MF-USMF150")
      (footprint "eagle-import:PFUF_1210POLY")
      (libsource (lib "eagle-import") (part "PFUF"))
    )
    (comp (ref "IC3")
      (value "TPS54240DGQR")
      (footprint "eagle-import:S-PDSO-G10")
      (libsource (lib "eagle-import") (part "TPS54240DGQR"))
    )
    (comp (ref "IC4")
      (value "TPS54240DGQR")
      (footprint "eagle-import:S-PDSO-G10")
      (libsource (lib "eagle-import") (part "TPS54240DGQR"))
    )
    (comp (ref "L3")
      (value "PIS4728-220M-04")
      (footprint "eagle-import:DR127")
      (libsource (lib "eagle-import") (part "DR127"))
    )
    (comp (ref "L4")
      (value "PIS4728-220M-04")
      (footprint "eagle-import:DR127")
      (libsource (lib "eagle-import") (part "DR127"))
    )
    (comp (ref "LED3")
      (value "(n.b.)")
      (footprint "eagle-import:CHIPLED_0805")
      (libsource (lib "eagle-import") (part "LEDCHIPLED_0805"))
    )
    (comp (ref "LED4")
      (value "(n.b.)")
      (footprint "eagle-import:CHIPLED_0805")
      (libsource (lib "eagle-import") (part "LEDCHIPLED_0805"))
    )
    (comp (ref "LSP1")
      (value "(n.b.)SE13")
      (footprint "eagle-import:SE13")
      (libsource (lib "eagle-import") (part "SE13"))
    )
    (comp (ref "LSP2")
      (value "(n.b.)SE13")
      (footprint "eagle-import:SE13")
      (libsource (lib "eagle-import") (part "SE13"))
    )
    (comp (ref "R43")
      (value "100K")
      (footprint "eagle-import:R0805")
      (libsource (lib "eagle-import") (part "resistor_R-EU_R0805"))
    )
    (comp (ref "R44")
      (value "100K")
      (footprint "eagle-import:R0805")
      (libsource (lib "eagle-import") (part "resistor_R-EU_R0805"))
    )
    (comp (ref "R45")
      (value "348K")
      (footprint "eagle-import:R0805")
      (libsource (lib "eagle-import") (part "resistor_R-EU_R0805"))
    )
    (comp (ref "R46")
      (value "348K")
      (footprint "eagle-import:R0805")
      (libsource (lib "eagle-import") (part "resistor_R-EU_R0805"))
    )
    (comp (ref "R47")
      (value "0")
      (footprint "eagle-import:R0805")
      (libsource (lib "eagle-import") (part "resistor_R-EU_R0805"))
    )
    (comp (ref "R48")
      (value "0")
      (footprint "eagle-import:R0805")
      (libsource (lib "eagle-import") (part "resistor_R-EU_R0805"))
    )
    (comp (ref "R49")
      (value "39K")
      (footprint "eagle-import:R0805")
      (libsource (lib "eagle-import") (part "resistor_R-EU_R0805"))
    )
    (comp (ref "R50")
      (value "39K")
      (footprint "eagle-import:R0805")
      (libsource (lib "eagle-import") (part "resistor_R-EU_R0805"))
    )
    (comp (ref "R51")
      (value "0")
      (footprint "eagle-import:R0805")
      (libsource (lib "eagle-import") (part "resistor_R-EU_R0805"))
    )
    (comp (ref "R52")
      (value "0")
      (footprint "eagle-import:R0805")
      (libsource (lib "eagle-import") (part "resistor_R-EU_R0805"))
    )
    (comp (ref "R53")
      (value "0")
      (footprint "eagle-import:R0805")
      (libsource (lib "eagle-import") (part "resistor_R-EU_R0805"))
    )
    (comp (ref "R54")
      (value "53K")
      (footprint "eagle-import:R0805")
      (libsource (lib "eagle-import") (part "resistor_R-EU_R0805"))
    )
    (comp (ref "R55")
      (value "10k")
      (footprint "eagle-import:R0805")
      (libsource (lib "eagle-import") (part "resistor_R-EU_R0805"))
    )
    (comp (ref "R56")
      (value "0")
      (footprint "eagle-import:R0805")
      (libsource (lib "eagle-import") (part "resistor_R-EU_R0805"))
    )
    (comp (ref "R57")
      (value "53K")
      (footprint "eagle-import:R0805")
      (libsource (lib "eagle-import") (part "resistor_R-EU_R0805"))
    )
    (comp (ref "R58")
      (value "10K")
      (footprint "eagle-import:R0805")
      (libsource (lib "eagle-import") (part "resistor_R-EU_R0805"))
    )
    (comp (ref "R59")
      (value "(n.b.)")
      (footprint "eagle-import:R0805")
      (libsource (lib "eagle-import") (part "resistor_R-EU_R0805"))
    )
    (comp (ref "R60")
      (value "(n.b.)")
      (footprint "eagle-import:R0805")
      (libsource (lib "eagle-import") (part "resistor_R-EU_R0805"))
    )
    (comp (ref "X10")
      (value "MKDS1/4-3,81")
      (footprint "eagle-import:4POL381")
      (libsource (lib "eagle-import") (part "MKDS1/4-3,81"))
    )
    (comp (ref "C12")
      (value "100n")
      (footprint "eagle-import:0805")
      (libsource (lib "eagle-import") (part "C_SMD0805"))
    )
    (comp (ref "C13")
      (value "1u")
      (footprint "eagle-import:0805")
      (libsource (lib "eagle-import") (part "C_SMD0805"))
    )
    (comp (ref "C14")
      (value "12p")
      (footprint "eagle-import:0805")
      (libsource (lib "eagle-import") (part "C_SMD0805"))
    )
    (comp (ref "C15")
      (value "18p")
      (footprint "eagle-import:0805")
      (libsource (lib "eagle-import") (part "C_SMD0805"))
    )
    (comp (ref "C16")
      (value "100n")
      (footprint "eagle-import:0805")
      (libsource (lib "eagle-import") (part "C_SMD0805"))
    )
    (comp (ref "C17")
      (value "100n")
      (footprint "eagle-import:0805")
      (libsource (lib "eagle-import") (part "C_SMD0805"))
    )
    (comp (ref "C18")
      (value "100n")
      (footprint "eagle-import:0805")
      (libsource (lib "eagle-import") (part "C_SMD0805"))
    )
    (comp (ref "C19")
      (value "12p")
      (footprint "eagle-import:0805")
      (libsource (lib "eagle-import") (part "C_SMD0805"))
    )
    (comp (ref "C20")
      (value "18p")
      (footprint "eagle-import:0805")
      (libsource (lib "eagle-import") (part "C_SMD0805"))
    )
    (comp (ref "C21")
      (value "10µ")
      (footprint "eagle-import:0805")
      (libsource (lib "eagle-import") (part "C_SMD0805"))
    )
    (comp (ref "C22")
      (value "100n")
      (footprint "eagle-import:0805")
      (libsource (lib "eagle-import") (part "C_SMD0805"))
    )
    (comp (ref "C23")
      (value "100n")
      (footprint "eagle-import:0805")
      (libsource (lib "eagle-import") (part "C_SMD0805"))
    )
    (comp (ref "C24")
      (value "100n")
      (footprint "eagle-import:0805")
      (libsource (lib "eagle-import") (part "C_SMD0805"))
    )
    (comp (ref "C25")
      (value "100n")
      (footprint "eagle-import:0805")
      (libsource (lib "eagle-import") (part "C_SMD0805"))
    )
    (comp (ref "C26")
      (value "100n")
      (footprint "eagle-import:0805")
      (libsource (lib "eagle-import") (part "C_SMD0805"))
    )
    (comp (ref "C27")
      (value "10µ")
      (footprint "eagle-import:0805")
      (libsource (lib "eagle-import") (part "C_SMD0805"))
    )
    (comp (ref "IC2")
      (value "EFM32G230F128")
      (footprint "eagle-import:QFN64")
      (libsource (lib "eagle-import") (part "EFM32G230F128"))
    )
    (comp (ref "L2")
      (value "BLM21B102S")
      (footprint "eagle-import:0805")
      (fields (field (name "MPN") "7427920"))
      (libsource (lib "eagle-import") (part "WE-CBF_0805-7427920"))
    )
    (comp (ref "Q2")
      (value "NX5032GA/32MHz/8pF")
      (footprint "eagle-import:CRYSTAL2P5.0X3.2")
      (libsource (lib "eagle-import") (part "CRYSTAL2P5.0X3.2"))
    )
    (comp (ref "Q3")
      (value "CM7V, 32768Hz/12.5pF")
      (footprint "eagle-import:CRYSTAL2P3.2X1.5")
      (libsource (lib "eagle-import") (part "CRYSTAL2P"))
    )
    (comp (ref "R11")
      (value "1")
      (footprint "eagle-import:R0805")
      (libsource (lib "eagle-import") (part "R-EU_R0805"))
    )
  )
  (nets
    (net (code "1") (name "AVDD") (class "Default")
      (node (ref "C21") (pin "2") (pinfunction "2_2") (pintype "passive"))
      (node (ref "C23") (pin "2") (pinfunction "2_2") (pintype "passive"))
      (node (ref "C25") (pin "2") (pinfunction "2_2") (pintype "passive"))
      (node (ref "IC2") (pin "23") (pinfunction "AVDD_1_23") (pintype "power_in"))
      (node (ref "IC2") (pin "27") (pinfunction "AVDD_0_27") (pintype "power_in"))
      (node (ref "R11") (pin "2") (pinfunction "2_2") (pintype "passive"))
    )
    (net (code "2") (name "BATT_INPUT") (class "Default")
      (node (ref "C1") (pin "+") (pinfunction "+_+") (pintype "passive"))
      (node (ref "C2") (pin "1") (pinfunction "1_1") (pintype "passive"))
      (node (ref "F3") (pin "P$1") (pinfunction "1_P$1") (pintype "passive"))
      (node (ref "F4") (pin "P$1") (pinfunction "1_P$1") (pintype "passive"))
      (node (ref "IC1") (pin "2") (pinfunction "VIN_2") (pintype "passive"))
      (node (ref "Q1") (pin "1") (pinfunction "S_1") (pintype "passive"))
      (node (ref "Q1") (pin "2") (pinfunction "S_2") (pintype "passive"))
      (node (ref "Q1") (pin "3") (pinfunction "S_3") (pintype "passive"))
      (node (ref "R3") (pin "2") (pinfunction "2_2") (pintype "passive"))
      (node (ref "R63") (pin "2") (pinfunction "2_2") (pintype "passive"))
      (node (ref "R64") (pin "2") (pinfunction "2_2") (pintype "passive"))
      (node (ref "T12") (pin "2") (pinfunction "S_2") (pintype "passive"))
      (node (ref "T13") (pin "2") (pinfunction "S_2") (pintype "passive"))
    )
    (net (code "3") (name "GND") (class "Default")
      (node (ref "C1") (pin "-") (pinfunction "-_-") (pintype "passive"))
      (node (ref "C10") (pin "2") (pinfunction "2_2") (pintype "passive"))
      (node (ref "C11") (pin "1") (pinfunction "1_1") (pintype "passive"))
      (node (ref "C12") (pin "1") (pinfunction "1_1") (pintype "passive"))
      (node (ref "C13") (pin "1") (pinfunction "1_1") (pintype "passive"))
      (node (ref "C14") (pin "1") (pinfunction "1_1") (pintype "passive"))
      (node (ref "C15") (pin "1") (pinfunction "1_1") (pintype "passive"))
      (node (ref "C16") (pin "1") (pinfunction "1_1") (pintype "passive"))
      (node (ref "C17") (pin "1") (pinfunction "1_1") (pintype "passive"))
      (node (ref "C18") (pin "1") (pinfunction "1_1") (pintype "passive"))
      (node (ref "C19") (pin "1") (pinfunction "1_1") (pintype "passive"))
      (node (ref "C2") (pin "2") (pinfunction "2_2") (pintype "passive"))
      (node (ref "C20") (pin "1") (pinfunction "1_1") (pintype "passive"))
      (node (ref "C21") (pin "1") (pinfunction "1_1") (pintype "passive"))
      (node (ref "C22") (pin "1") (pinfunction "1_1") (pintype "passive"))
      (node (ref "C23") (pin "1") (pinfunction "1_1") (pintype "passive"))
      (node (ref "C24") (pin "1") (pinfunction "1_1") (pintype "passive"))
      (node (ref "C25") (pin "1") (pinfunction "1_1") (pintype "passive"))
      (node (ref "C26") (pin "1") (pinfunction "1_1") (pintype "passive"))
      (node (ref "C27") (pin "1") (pinfunction "1_1") (pintype "passive"))
      (node (ref "C28") (pin "2") (pinfunction "2_2") (pintype "passive"))
      (node (ref "C29") (pin "2") (pinfunction "2_2") (pintype "passive"))
      (node (ref "C3") (pin "2") (pinfunction "2_2") (pintype "passive"))
      (node (ref "C30") (pin "2") (pinfunction "2_2") (pintype "passive"))
      (node (ref "C31") (pin "2") (pinfunction "2_2") (pintype "passive"))
      (node (ref "C32") (pin "2") (pinfunction "2_2") (pintype "passive"))
      (node (ref "C33") (pin "2") (pinfunction "2_2") (pintype "passive"))
      (node (ref "C34") (pin "2") (pinfunction "2_2") (pintype "passive"))
      (node (ref "C35") (pin "2") (pinfunction "2_2") (pintype "passive"))
      (node (ref "C36") (pin "2") (pinfunction "2_2") (pintype "passive"))
      (node (ref "C37") (pin "2") (pinfunction "2_2") (pintype "passive"))
      (node (ref "C38") (pin "2") (pinfunction "2_2") (pintype "passive"))
      (node (ref "C4") (pin "-") (pinfunction "-_-") (pintype "passive"))
      (node (ref "C41") (pin "2") (pinfunction "2_2") (pintype "passive"))
      (node (ref "C42") (pin "2") (pinfunction "2_2") (pintype "passive"))
      (node (ref "C43") (pin "2") (pinfunction "2_2") (pintype "passive"))
      (node (ref "C44") (pin "2") (pinfunction "2_2") (pintype "passive"))
      (node (ref "C45") (pin "2") (pinfunction "2_2") (pintype "passive"))
      (node (ref "C46") (pin "2") (pinfunction "2_2") (pintype "passive"))
      (node (ref "C47") (pin "2") (pinfunction "2_2") (pintype "passive"))
      (node (ref "C48") (pin "2") (pinfunction "2_2") (pintype "passive"))
      (node (ref "C49") (pin "2") (pinfunction "2_2") (pintype "passive"))
      (node (ref "C5") (pin "-") (pinfunction "-_-") (pintype "passive"))
      (node (ref "C50") (pin "2") (pinfunction "2_2") (pintype "passive"))
      (node (ref "C51") (pin "2") (pinfunction "2_2") (pintype "passive"))
      (node (ref "C52") (pin "2") (pinfunction "2_2") (pintype "passive"))
      (node (ref "C53") (pin "2") (pinfunction "2_2") (pintype "passive"))
      (node (ref "C54") (pin "2") (pinfunction "2_2") (pintype "passive"))
      (node (ref "C55") (pin "2") (pinfunction "2_2") (pintype "passive"))
      (node (ref "C56") (pin "2") (pinfunction "2_2") (pintype "passive"))
      (node (ref "C57") (pin "1") (pinfunction "1_1") (pintype "passive"))
      (node (ref "C6") (pin "-") (pinfunction "-_-") (pintype "passive"))
      (node (ref "C7") (pin "-") (pinfunction "-_-") (pintype "passive"))
      (node (ref "C8") (pin "2") (pinfunction "2_2") (pintype "passive"))
      (node (ref "C9") (pin "2") (pinfunction "2_2") (pintype "passive"))
      (node (ref "D5") (pin "A") (pinfunction "A_A") (pintype "passive"))
      (node (ref "D6") (pin "A") (pinfunction "A_A") (pintype "passive"))
      (node (ref "IC1") (pin "1") (pinfunction "GND_1") (pintype "passive"))
      (node (ref "IC1") (pin "EXP") (pinfunction "EXP_EXP") (pintype "passive"))
      (node (ref "IC2") (pin "65") (pinfunction "VSS_65") (pintype "power_in"))
      (node (ref "IC3") (pin "9") (pinfunction "GND_9") (pintype "power_in"))
      (node (ref "IC3") (pin "EXP") (pinfunction "EXP_EXP") (pintype "power_in"))
      (node (ref "IC4") (pin "9") (pinfunction "GND_9") (pintype "power_in"))
      (node (ref "IC4") (pin "EXP") (pinfunction "EXP_EXP") (pintype "power_in"))
      (node (ref "J1") (pin "P$1") (pinfunction "1-SLEEVE_P$1") (pintype "bidirectional"))
      (node (ref "LED1") (pin "C") (pinfunction "C_C") (pintype "passive"))
      (node (ref "LED2") (pin "C") (pinfunction "C_C") (pintype "passive"))
      (node (ref "LED3") (pin "C") (pinfunction "C_C") (pintype "passive"))
      (node (ref "LED4") (pin "C") (pinfunction "C_C") (pintype "passive"))
      (node (ref "R1") (pin "1") (pinfunction "1_1") (pintype "passive"))
      (node (ref "R14") (pin "1") (pinfunction "1_1") (pintype "passive"))
      (node (ref "R18") (pin "1") (pinfunction "1_1") (pintype "passive"))
      (node (ref "R29") (pin "1") (pinfunction "1_1") (pintype "passive"))
      (node (ref "R30") (pin "1") (pinfunction "1_1") (pintype "passive"))
      (node (ref "R32") (pin "1") (pinfunction "1_1") (pintype "passive"))
      (node (ref "R35") (pin "1") (pinfunction "1_1") (pintype "passive"))
      (node (ref "R37") (pin "1") (pinfunction "1_1") (pintype "passive"))
      (node (ref "R40") (pin "1") (pinfunction "1_1") (pintype "passive"))
      (node (ref "R42") (pin "1") (pinfunction "1_1") (pintype "passive"))
      (node (ref "R43") (pin "1") (pinfunction "1_1") (pintype "passive"))
      (node (ref "R44") (pin "1") (pinfunction "1_1") (pintype "passive"))
      (node (ref "R45") (pin "1") (pinfunction "1_1") (pintype "passive"))
      (node (ref "R46") (pin "1") (pinfunction "1_1") (pintype "passive"))
      (node (ref "R5") (pin "1") (pinfunction "1_1") (pintype "passive"))
      (node (ref "R55") (pin "1") (pinfunction "1_1") (pintype "passive"))
      (node (ref "R58") (pin "1") (pinfunction "1_1") (pintype "passive"))
      (node (ref "R65") (pin "1") (pinfunction "1_1") (pintype "passive"))
      (node (ref "R66") (pin "1") (pinfunction "1_1") (pintype "passive"))
      (node (ref "R69") (pin "1") (pinfunction "1_1") (pintype "passive"))
      (node (ref "R70") (pin "1") (pinfunction "1_1") (pintype "passive"))
      (node (ref "R73") (pin "2") (pinfunction "2_2") (pintype "passive"))
      (node (ref "R9") (pin "1") (pinfunction "1_1") (pintype "passive"))
      (node (ref "SD1") (pin "3") (pinfunction "3_3") (pintype "bidirectional"))
      (node (ref "SD1") (pin "6") (pinfunction "6_6") (pintype "bidirectional"))
      (node (ref "SD1") (pin "COM") (pinfunction "COM_COM") (pintype "passive"))
      (node (ref "T1") (pin "2") (pinfunction "S_2") (pintype "passive"))
      (node (ref "T10") (pin "2") (pinfunction "S_2") (pintype "passive"))
      (node (ref "T11") (pin "2") (pinfunction "S_2") (pintype "passive"))
      (node (ref "T3") (pin "2") (pinfunction "S_2") (pintype "passive"))
      (node (ref "T5") (pin "2") (pinfunction "S_2") (pintype "passive"))
      (node (ref "T6") (pin "2") (pinfunction "S_2") (pintype "passive"))
      (node (ref "T8") (pin "2") (pinfunction "S_2") (pintype "passive"))
      (node (ref "X1") (pin "1") (pinfunction "1_1") (pintype "passive"))
      (node (ref "X10") (pin "2") (pinfunction "1_2") (pintype "passive"))
      (node (ref "X10") (pin "4") (pinfunction "1_4") (pintype "passive"))
      (node (ref "X14") (pin "2") (pinfunction "1_2") (pintype "passive"))
      (node (ref "X15") (pin "2") (pinfunction "1_2") (pintype "passive"))
      (node (ref "X2") (pin "3") (pinfunction "3_3") (pintype "passive"))
      (node (ref "X2") (pin "5") (pinfunction "5_5") (pintype "passive"))
      (node (ref "X3") (pin "1.3") (pinfunction "1_1.3") (pintype "passive"))
      (node (ref "X3") (pin "1.4") (pinfunction "1_1.4") (pintype "passive"))
      (node (ref "X4") (pin "2") (pinfunction "1_2") (pintype "passive"))
      (node (ref "X5") (pin "3") (pinfunction "1_3") (pintype "passive"))
      (node (ref "X6") (pin "3") (pinfunction "1_3") (pintype "passive"))
      (node (ref "X8") (pin "2") (pinfunction "1_2") (pintype "passive"))
      (node (ref "X8") (pin "4") (pinfunction "1_4") (pintype "passive"))
      (node (ref "X8") (pin "6") (pinfunction "1_6") (pintype "passive"))
    )
    (net (code "4") (name "MCU_RESET") (class "Default")
      (node (ref "C12") (pin "2") (pinfunction "2_2") (pintype "passive"))
      (node (ref "C57") (pin "2") (pinfunction "2_2") (pintype "passive"))
      (node (ref "IC2") (pin "20") (pinfunction "RESETN_20") (pintype "passive"))
      (node (ref "R74") (pin "1") (pinfunction "1_1") (pintype "passive"))
      (node (ref "S1") (pin "1") (pinfunction "1_1") (pintype "passive"))
      (node (ref "S1") (pin "2") (pinfunction "2_2") (pintype "passive"))
      (node (ref "X2") (pin "8") (pinfunction "8_8") (pintype "passive"))
    )
    (net (code "5") (name "Net-(C45-Pad1)") (class "Default")
      (node (ref "C45") (pin "1") (pinfunction "1_1") (pintype "passive"))
      (node (ref "C47") (pin "1") (pinfunction "1_1") (pintype "passive"))
      (node (ref "R51") (pin "1") (pinfunction "1_1") (pintype "passive"))
    )
    (net (code "6") (name "Net-(C46-Pad1)") (class "Default")
      (node (ref "C46") (pin "1") (pinfunction "1_1") (pintype "passive"))
      (node (ref "C48") (pin "1") (pinfunction "1_1") (pintype "passive"))
      (node (ref "R52") (pin "1") (pinfunction "1_1") (pintype "passive"))
    )
    (net (code "7") (name "Net-(D1-A1)") (class "Default")
      (node (ref "C3") (pin "1") (pinfunction "1_1") (pintype "passive"))
      (node (ref "D1") (pin "2") (pinfunction "A1_2") (pintype "passive"))
      (node (ref "D1") (pin "3") (pinfunction "A2_3") (pintype "passive"))
      (node (ref "D2") (pin "2") (pinfunction "A1_2") (pintype "passive"))
      (node (ref "D2") (pin "3") (pinfunction "A2_3") (pintype "passive"))
      (node (ref "D3") (pin "2") (pinfunction "A1_2") (pintype "passive"))
      (node (ref "D3") (pin "3") (pinfunction "A2_3") (pintype "passive"))
      (node (ref "D4") (pin "2") (pinfunction "A1_2") (pintype "passive"))
      (node (ref "IC1") (pin "6") (pinfunction "VOS_6") (pintype "input"))
      (node (ref "L1") (pin "2") (pinfunction "2_2") (pintype "passive"))
      (node (ref "R7") (pin "1") (pinfunction "1_1") (pintype "passive"))
      (node (ref "R8") (pin "2") (pinfunction "2_2") (pintype "passive"))
    )
    (net (code "8") (name "Net-(D4-A2)") (class "Default")
      (node (ref "C4") (pin "+") (pinfunction "+_+") (pintype "passive"))
      (node (ref "D4") (pin "3") (pinfunction "A2_3") (pintype "passive"))
      (node (ref "R10") (pin "2") (pinfunction "2_2") (pintype "passive"))
    )
    (net (code "9") (name "Net-(F3-2)") (class "Default")
      (node (ref "C34") (pin "1") (pinfunction "1_1") (pintype "passive"))
      (node (ref "C36") (pin "1") (pinfunction "1_1") (pintype "passive"))
      (node (ref "F3") (pin "P$2") (pinfunction "2_P$2") (pintype "passive"))
      (node (ref "IC4") (pin "2") (pinfunction "VIN_2") (pintype "input"))
    )
    (net (code "10") (name "Net-(F4-2)") (class "Default")
      (node (ref "C33") (pin "1") (pinfunction "1_1") (pintype "passive"))
      (node (ref "C35") (pin "1") (pinfunction "1_1") (pintype "passive"))
      (node (ref "F4") (pin "P$2") (pinfunction "2_P$2") (pintype "passive"))
      (node (ref "IC3") (pin "2") (pinfunction "VIN_2") (pintype "input"))
    )
    (net (code "11") (name "Net-(IC1-EN)") (class "Default")
      (node (ref "IC1") (pin "3") (pinfunction "EN_3") (pintype "input"))
      (node (ref "R3") (pin "1") (pinfunction "1_1") (pintype "passive"))
      (node (ref "R4") (pin "2") (pinfunction "2_2") (pintype "passive"))
    )
    (net (code "12") (name "Net-(IC1-ENHYS)") (class "Default")
      (node (ref "IC1") (pin "4") (pinfunction "ENHYS_4") (pintype "output"))
      (node (ref "R4") (pin "1") (pinfunction "1_1") (pintype "passive"))
      (node (ref "R5") (pin "2") (pinfunction "2_2") (pintype "passive"))
    )
    (net (code "13") (name "Net-(IC1-FB)") (class "Default")
      (node (ref "IC1") (pin "5") (pinfunction "FB_5") (pintype "input"))
      (node (ref "R8") (pin "1") (pinfunction "1_1") (pintype "passive"))
      (node (ref "R9") (pin "2") (pinfunction "2_2") (pintype "passive"))
    )
    (net (code "14") (name "Net-(IC1-SW)") (class "Default")
      (node (ref "IC1") (pin "7") (pinfunction "SW_7") (pintype "output"))
      (node (ref "L1") (pin "1") (pinfunction "1_1") (pintype "passive"))
    )
    (net (code "15") (name "Net-(IC2G-DECOUPLE)") (class "Default")
      (node (ref "C13") (pin "2") (pinfunction "2_2") (pintype "passive"))
      (node (ref "IC2") (pin "40") (pinfunction "DECOUPLE_40") (pintype "power_in"))
    )
    (net (code "16") (name "Net-(IC3-BOOT)") (class "Default")
      (node (ref "C39") (pin "2") (pinfunction "2_2") (pintype "passive"))
      (node (ref "IC3") (pin "1") (pinfunction "BOOT_1") (pintype "output"))
    )
    (net (code "17") (name "Net-(IC3-COMP)") (class "Default")
      (node (ref "C41") (pin "1") (pinfunction "1_1") (pintype "passive"))
      (node (ref "C43") (pin "1") (pinfunction "1_1") (pintype "passive"))
      (node (ref "IC3") (pin "8") (pinfunction "COMP_8") (pintype "input"))
      (node (ref "R49") (pin "1") (pinfunction "1_1") (pintype "passive"))
    )
    (net (code "18") (name "Net-(IC3-PH)") (class "Default")
      (node (ref "C39") (pin "1") (pinfunction "1_1") (pintype "passive"))
      (node (ref "D5") (pin "C") (pinfunction "C_C") (pintype "passive"))
      (node (ref "IC3") (pin "10") (pinfunction "PH_10") (pintype "output"))
      (node (ref "L3") (pin "1") (pinfunction "1_1") (pintype "passive"))
    )
    (net (code "19") (name "Net-(IC3-RT{slash}CLK)") (class "Default")
      (node (ref "IC3") (pin "5") (pinfunction "RT/CLK_5") (pintype "input"))
      (node (ref "R47") (pin "2") (pinfunction "2_2") (pintype "passive"))
    )
    (net (code "20") (name "Net-(IC3-SS{slash}TR)") (class "Default")
      (node (ref "C37") (pin "1") (pinfunction "1_1") (pintype "passive"))
      (node (ref "IC3") (pin "4") (pinfunction "SS/TR_4") (pintype "input"))
    )
    (net (code "21") (name "Net-(IC3-VSNS)") (class "Default")
      (node (ref "IC3") (pin "7") (pinfunction "VSNS_7") (pintype "input"))
      (node (ref "R54") (pin "1") (pinfunction "1_1") (pintype "passive"))
      (node (ref "R55") (pin "2") (pinfunction "2_2") (pintype "passive"))
    )
    (net (code "22") (name "Net-(IC4-BOOT)") (class "Default")
      (node (ref "C40") (pin "2") (pinfunction "2_2") (pintype "passive"))
      (node (ref "IC4") (pin "1") (pinfunction "BOOT_1") (pintype "output"))
    )
    (net (code "23") (name "Net-(IC4-COMP)") (class "Default")
      (node (ref "C42") (pin "1") (pinfunction "1_1") (pintype "passive"))
      (node (ref "C44") (pin "1") (pinfunction "1_1") (pintype "passive"))
      (node (ref "IC4") (pin "8") (pinfunction "COMP_8") (pintype "input"))
      (node (ref "R50") (pin "1") (pinfunction "1_1") (pintype "passive"))
    )
    (net (code "24") (name "Net-(IC4-PH)") (class "Default")
      (node (ref "C40") (pin "1") (pinfunction "1_1") (pintype "passive"))
      (node (ref "D6") (pin "C") (pinfunction "C_C") (pintype "passive"))
      (node (ref "IC4") (pin "10") (pinfunction "PH_10") (pintype "output"))
      (node (ref "L4") (pin "1") (pinfunction "1_1") (pintype "passive"))
    )
    (net (code "25") (name "Net-(IC4-RT{slash}CLK)") (class "Default")
      (node (ref "IC4") (pin "5") (pinfunction "RT/CLK_5") (pintype "input"))
      (node (ref "R48") (pin "2") (pinfunction "2_2") (pintype "passive"))
    )
    (net (code "26") (name "Net-(IC4-SS{slash}TR)") (class "Default")
      (node (ref "C38") (pin "1") (pinfunction "1_1") (pintype "passive"))
      (node (ref "IC4") (pin "4") (pinfunction "SS/TR_4") (pintype "input"))
    )
    (net (code "27") (name "Net-(IC4-VSNS)") (class "Default")
      (node (ref "IC4") (pin "7") (pinfunction "VSNS_7") (pintype "input"))
      (node (ref "R57") (pin "1") (pinfunction "1_1") (pintype "passive"))
      (node (ref "R58") (pin "2") (pinfunction "2_2") (pintype "passive"))
    )
    (net (code "28") (name "Net-(L2-Pad2)") (class "Default")
      (node (ref "L2") (pin "2") (pinfunction "2_2") (pintype "passive"))
      (node (ref "R11") (pin "1") (pinfunction "1_1") (pintype "passive"))
    )
    (net (code "29") (name "Net-(LED1-PadA)") (class "Default")
      (node (ref "LED1") (pin "A") (pinfunction "A_A") (pintype "passive"))
      (node (ref "R2") (pin "2") (pinfunction "2_2") (pintype "passive"))
    )
    (net (code "30") (name "Net-(LED2-PadA)") (class "Default")
      (node (ref "LED2") (pin "A") (pinfunction "A_A") (pintype "passive"))
      (node (ref "R6") (pin "2") (pinfunction "2_2") (pintype "passive"))
    )
    (net (code "31") (name "Net-(LED3-PadA)") (class "Default")
      (node (ref "LED3") (pin "A") (pinfunction "A_A") (pintype "passive"))
      (node (ref "R59") (pin "1") (pinfunction "1_1") (pintype "passive"))
    )
    (net (code "32") (name "Net-(LED4-PadA)") (class "Default")
      (node (ref "LED4") (pin "A") (pinfunction "A_A") (pintype "passive"))
      (node (ref "R60") (pin "1") (pinfunction "1_1") (pintype "passive"))
    )
    (net (code "33") (name "Net-(Q1-G)") (class "Default")
      (node (ref "Q1") (pin "4") (pinfunction "G_4") (pintype "passive"))
      (node (ref "R1") (pin "2") (pinfunction "2_2") (pintype "passive"))
    )
    (net (code "34") (name "Net-(R19-Pad1)") (class "Default")
      (node (ref "R19") (pin "1") (pinfunction "1_1") (pintype "passive"))
      (node (ref "SD1") (pin "8") (pinfunction "8_8") (pintype "bidirectional"))
    )
    (net (code "35") (name "Net-(R20-Pad1)") (class "Default")
      (node (ref "R20") (pin "1") (pinfunction "1_1") (pintype "passive"))
      (node (ref "SD1") (pin "9") (pinfunction "9_9") (pintype "bidirectional"))
    )
    (net (code "36") (name "Net-(R45-Pad2)") (class "Default")
      (node (ref "R45") (pin "2") (pinfunction "2_2") (pintype "passive"))
      (node (ref "R47") (pin "1") (pinfunction "1_1") (pintype "passive"))
    )
    (net (code "37") (name "Net-(R46-Pad2)") (class "Default")
      (node (ref "R46") (pin "2") (pinfunction "2_2") (pintype "passive"))
      (node (ref "R48") (pin "1") (pinfunction "1_1") (pintype "passive"))
    )
    (net (code "38") (name "Net-(R49-Pad2)") (class "Default")
      (node (ref "R49") (pin "2") (pinfunction "2_2") (pintype "passive"))
      (node (ref "R51") (pin "2") (pinfunction "2_2") (pintype "passive"))
    )
    (net (code "39") (name "Net-(R50-Pad2)") (class "Default")
      (node (ref "R50") (pin "2") (pinfunction "2_2") (pintype "passive"))
      (node (ref "R52") (pin "2") (pinfunction "2_2") (pintype "passive"))
    )
    (net (code "40") (name "Net-(R53-Pad1)") (class "Default")
      (node (ref "R53") (pin "1") (pinfunction "1_1") (pintype "passive"))
      (node (ref "R54") (pin "2") (pinfunction "2_2") (pintype "passive"))
    )
    (net (code "41") (name "Net-(R56-Pad1)") (class "Default")
      (node (ref "R56") (pin "1") (pinfunction "1_1") (pintype "passive"))
      (node (ref "R57") (pin "2") (pinfunction "2_2") (pintype "passive"))
    )
    (net (code "42") (name "Net-(R73-Pad1)") (class "Default")
      (node (ref "R73") (pin "1") (pinfunction "1_1") (pintype "passive"))
      (node (ref "S1") (pin "3") (pinfunction "3_3") (pintype "passive"))
      (node (ref "S1") (pin "4") (pinfunction "4_4") (pintype "passive"))
    )
    (net (code "43") (name "Net-(T1-D)") (class "Default")
      (node (ref "R16") (pin "1") (pinfunction "1_1") (pintype "passive"))
      (node (ref "T1") (pin "1") (pinfunction "D_1") (pintype "passive"))
    )
    (net (code "44") (name "Net-(T1-G)") (class "Default")
      (node (ref "R12") (pin "1") (pinfunction "1_1") (pintype "passive"))
      (node (ref "R14") (pin "2") (pinfunction "2_2") (pintype "passive"))
      (node (ref "T1") (pin "3") (pinfunction "G_3") (pintype "passive"))
    )
    (net (code "45") (name "Net-(T2-G)") (class "Default")
      (node (ref "R13") (pin "1") (pinfunction "1_1") (pintype "passive"))
      (node (ref "R16") (pin "2") (pinfunction "2_2") (pintype "passive"))
      (node (ref "T2") (pin "3") (pinfunction "G_3") (pintype "passive"))
    )
    (net (code "46") (name "Net-(T3-D)") (class "Default")
      (node (ref "R31") (pin "1") (pinfunction "1_1") (pintype "passive"))
      (node (ref "T3") (pin "1") (pinfunction "D_1") (pintype "passive"))
    )
    (net (code "47") (name "Net-(T3-G)") (class "Default")
      (node (ref "R26") (pin "1") (pinfunction "1_1") (pintype "passive"))
      (node (ref "R29") (pin "2") (pinfunction "2_2") (pintype "passive"))
      (node (ref "T3") (pin "3") (pinfunction "G_3") (pintype "passive"))
    )
    (net (code "48") (name "Net-(T4-G)") (class "Default")
      (node (ref "R28") (pin "1") (pinfunction "1_1") (pintype "passive"))
      (node (ref "R31") (pin "2") (pinfunction "2_2") (pintype "passive"))
      (node (ref "T4") (pin "3") (pinfunction "G_3") (pintype "passive"))
    )
    (net (code "49") (name "Net-(T5-G)") (class "Default")
      (node (ref "R27") (pin "2") (pinfunction "2_2") (pintype "passive"))
      (node (ref "R30") (pin "2") (pinfunction "2_2") (pintype "passive"))
      (node (ref "T5") (pin "3") (pinfunction "G_3") (pintype "passive"))
    )
    (net (code "50") (name "Net-(T6-D)") (class "Default")
      (node (ref "R36") (pin "1") (pinfunction "1_1") (pintype "passive"))
      (node (ref "T6") (pin "1") (pinfunction "D_1") (pintype "passive"))
    )
    (net (code "51") (name "Net-(T6-G)") (class "Default")
      (node (ref "R33") (pin "1") (pinfunction "1_1") (pintype "passive"))
      (node (ref "R35") (pin "2") (pinfunction "2_2") (pintype "passive"))
      (node (ref "T6") (pin "3") (pinfunction "G_3") (pintype "passive"))
    )
    (net (code "52") (name "Net-(T7-G)") (class "Default")
      (node (ref "R34") (pin "1") (pinfunction "1_1") (pintype "passive"))
      (node (ref "R36") (pin "2") (pinfunction "2_2") (pintype "passive"))
      (node (ref "T7") (pin "3") (pinfunction "G_3") (pintype "passive"))
    )
    (net (code "53") (name "Net-(T8-D)") (class "Default")
      (node (ref "R41") (pin "1") (pinfunction "1_1") (pintype "passive"))
      (node (ref "T8") (pin "1") (pinfunction "D_1") (pintype "passive"))
    )
    (net (code "54") (name "Net-(T8-G)") (class "Default")
      (node (ref "R38") (pin "1") (pinfunction "1_1") (pintype "passive"))
      (node (ref "R40") (pin "2") (pinfunction "2_2") (pintype "passive"))
      (node (ref "T8") (pin "3") (pinfunction "G_3") (pintype "passive"))
    )
    (net (code "55") (name "Net-(T9-G)") (class "Default")
      (node (ref "R39") (pin "1") (pinfunction "1_1") (pintype "passive"))
      (node (ref "R41") (pin "2") (pinfunction "2_2") (pintype "passive"))
      (node (ref "T9") (pin "3") (pinfunction "G_3") (pintype "passive"))
    )
    (net (code "56") (name "Net-(T10-D)") (class "Default")
      (node (ref "R67") (pin "1") (pinfunction "1_1") (pintype "passive"))
      (node (ref "T10") (pin "1") (pinfunction "D_1") (pintype "passive"))
    )
    (net (code "57") (name "Net-(T10-G)") (class "Default")
      (node (ref "R61") (pin "1") (pinfunction "1_1") (pintype "passive"))
      (node (ref "R65") (pin "2") (pinfunction "2_2") (pintype "passive"))
      (node (ref "T10") (pin "3") (pinfunction "G_3") (pintype "passive"))
    )
    (net (code "58") (name "Net-(T11-D)") (class "Default")
      (node (ref "R68") (pin "1") (pinfunction "1_1") (pintype "passive"))
      (node (ref "T11") (pin "1") (pinfunction "D_1") (pintype "passive"))
    )
    (net (code "59") (name "Net-(T11-G)") (class "Default")
      (node (ref "R62") (pin "1") (pinfunction "1_1") (pintype "passive"))
      (node (ref "R66") (pin "2") (pinfunction "2_2") (pintype "passive"))
      (node (ref "T11") (pin "3") (pinfunction "G_3") (pintype "passive"))
    )
    (net (code "60") (name "Net-(T12-G)") (class "Default")
      (node (ref "R63") (pin "1") (pinfunction "1_1") (pintype "passive"))
      (node (ref "R67") (pin "2") (pinfunction "2_2") (pintype "passive"))
      (node (ref "T12") (pin "3") (pinfunction "G_3") (pintype "passive"))
    )
    (net (code "61") (name "Net-(T13-G)") (class "Default")
      (node (ref "R64") (pin "1") (pinfunction "1_1") (pintype "passive"))
      (node (ref "R68") (pin "2") (pinfunction "2_2") (pintype "passive"))
      (node (ref "T13") (pin "3") (pinfunction "G_3") (pintype "passive"))
    )
    (net (code "62") (name "PA0_SMBUS_SDA") (class "Default")
      (node (ref "IC2") (pin "1") (pinfunction "PA0/I2C0_SDA#0/TIM0_CC0#0,1_1") (pintype "bidirectional"))
      (node (ref "R15") (pin "1") (pinfunction "1_1") (pintype "passive"))
      (node (ref "X5") (pin "1") (pinfunction "1_1") (pintype "passive"))
    )
    (net (code "63") (name "PA1_SMBUS_SCL") (class "Default")
      (node (ref "IC2") (pin "2") (pinfunction "PA1/CMU_CLK1#0/I2C0_SCL#0/TIM0_CC1#0,1_2") (pintype "bidirectional"))
      (node (ref "R17") (pin "1") (pinfunction "1_1") (pintype "passive"))
      (node (ref "X5") (pin "2") (pinfunction "1_2") (pintype "passive"))
    )
    (net (code "64") (name "PA2_POWER_LED") (class "Default")
      (node (ref "IC2") (pin "3") (pinfunction "PA2/CMU_CLK0#0/TIM0_CC2#0,1_3") (pintype "bidirectional"))
      (node (ref "R2") (pin "1") (pinfunction "1_1") (pintype "passive"))
    )
    (net (code "65") (name "PA3_CAM1_ENABLE") (class "Default")
      (node (ref "IC2") (pin "4") (pinfunction "PA3/TIM0_CDTI0#0_4") (pintype "bidirectional"))
      (node (ref "IC3") (pin "3") (pinfunction "ENA_3") (pintype "input"))
      (node (ref "R43") (pin "2") (pinfunction "2_2") (pintype "passive"))
    )
    (net (code "66") (name "PA4_CAM2_ENABLE") (class "Default")
      (node (ref "IC2") (pin "5") (pinfunction "PA4/TIM0_CDTI1#0_5") (pintype "bidirectional"))
      (node (ref "IC4") (pin "3") (pinfunction "ENA_3") (pintype "input"))
      (node (ref "R44") (pin "2") (pinfunction "2_2") (pintype "passive"))
    )
    (net (code "67") (name "PA5_LOG_FLUSH_LED") (class "Default")
      (node (ref "IC2") (pin "6") (pinfunction "PA5/LEU1_TX#1/TIM0_CDTI2#0_6") (pintype "bidirectional"))
      (node (ref "R6") (pin "1") (pinfunction "1_1") (pintype "passive"))
    )
    (net (code "68") (name "PA6_RFID_POWER") (class "Default")
      (node (ref "IC2") (pin "7") (pinfunction "PA6/LEU1_RX#1_7") (pintype "bidirectional"))
      (node (ref "R27") (pin "1") (pinfunction "1_1") (pintype "passive"))
    )
    (net (code "69") (name "PA8_RFID1_DATA") (class "Default")
      (node (ref "IC2") (pin "17") (pinfunction "PA8/TIM2_CC0#0_17") (pintype "bidirectional"))
      (node (ref "X7") (pin "1") (pinfunction "1_1") (pintype "passive"))
    )
    (net (code "70") (name "PA9_RFID2_DATA") (class "Default")
      (node (ref "IC2") (pin "18") (pinfunction "PA9/TIM2_CC1#0_18") (pintype "bidirectional"))
      (node (ref "X7") (pin "2") (pinfunction "1_2") (pintype "passive"))
    )
    (net (code "71") (name "PA10_RFID3_DATA") (class "Default")
      (node (ref "IC2") (pin "19") (pinfunction "PA10/TIM2_CC2#0_19") (pintype "bidirectional"))
      (node (ref "X7") (pin "3") (pinfunction "1_3") (pintype "passive"))
    )
    (net (code "72") (name "PB7_LFXTAL_P") (class "Default")
      (node (ref "C20") (pin "2") (pinfunction "2_2") (pintype "passive"))
      (node (ref "IC2") (pin "15") (pinfunction "PB7/LFXTAL_P/US1_CLK#0_15") (pintype "bidirectional"))
      (node (ref "Q3") (pin "2") (pinfunction "2_2") (pintype "passive"))
    )
    (net (code "73") (name "PB8_LFXTAL_N") (class "Default")
      (node (ref "C15") (pin "2") (pinfunction "2_2") (pintype "passive"))
      (node (ref "IC2") (pin "16") (pinfunction "PB8/LFXTAL_N/US1_CS#0_16") (pintype "bidirectional"))
      (node (ref "Q3") (pin "1") (pinfunction "1_1") (pintype "passive"))
    )
    (net (code "74") (name "PB11_POWER_GOOD") (class "Default")
      (node (ref "IC1") (pin "8") (pinfunction "PG_8") (pintype "output"))
      (node (ref "IC2") (pin "21") (pinfunction "PB11/DAC0_OUT0/OPAMP_OUT0/LETIM0_OUT0#1_21") (pintype "bidirectional"))
      (node (ref "R7") (pin "2") (pinfunction "2_2") (pintype "passive"))
    )
    (net (code "75") (name "PB12_N_SCHALTER_ZU") (class "Default")
      (node (ref "IC2") (pin "22") (pinfunction "PB12/DAC0_OUT1/OPAMP_OUT1/LETIM0_OUT1#1_22") (pintype "bidirectional"))
      (node (ref "X13") (pin "2") (pinfunction "1_2") (pintype "passive"))
    )
    (net (code "76") (name "PB13_HFXTAL_P") (class "Default")
      (node (ref "C19") (pin "2") (pinfunction "2_2") (pintype "passive"))
      (node (ref "IC2") (pin "24") (pinfunction "PB13/HFXTAL_P/LEU0_TX#1_24") (pintype "bidirectional"))
      (node (ref "Q2") (pin "2") (pinfunction "2_2") (pintype "passive"))
    )
    (net (code "77") (name "PB14_HFXTAL_N") (class "Default")
      (node (ref "C14") (pin "2") (pinfunction "2_2") (pintype "passive"))
      (node (ref "IC2") (pin "25") (pinfunction "PB14/HFXTAL_N/LEU0_RX#1_25") (pintype "bidirectional"))
      (node (ref "Q2") (pin "1") (pinfunction "1_1") (pintype "passive"))
    )
    (net (code "78") (name "PC0_RFID_RX") (class "Default")
      (node (ref "IC2") (pin "9") (pinfunction "PC0/ACMP0_CH0/PCNT0_S0IN#2/US1_TX#0_9") (pintype "bidirectional"))
      (node (ref "X9") (pin "1") (pinfunction "1_1") (pintype "passive"))
    )
    (net (code "79") (name "PC1_RFID_TX") (class "Default")
      (node (ref "IC2") (pin "10") (pinfunction "PC1/ACMP0_CH1/PCNT0_S1IN#2/US1_RX#0_10") (pintype "bidirectional"))
      (node (ref "X9") (pin "2") (pinfunction "1_2") (pintype "passive"))
    )
    (net (code "80") (name "PC2_SD_SDO") (class "Default")
      (node (ref "IC2") (pin "11") (pinfunction "PC2/ACMP0_CH2/US2_TX_11") (pintype "bidirectional"))
      (node (ref "SD1") (pin "2") (pinfunction "2_2") (pintype "bidirectional"))
    )
    (net (code "81") (name "PC3_SD_SDI") (class "Default")
      (node (ref "IC2") (pin "12") (pinfunction "PC3/ACMP0_CH3/US2_RX_12") (pintype "bidirectional"))
      (node (ref "R22") (pin "1") (pinfunction "1_1") (pintype "passive"))
      (node (ref "SD1") (pin "7") (pinfunction "7_7") (pintype "bidirectional"))
    )
    (net (code "82") (name "PC4_SD_CLK") (class "Default")
      (node (ref "IC2") (pin "13") (pinfunction "PC4/ACMP0_CH4/LETIM0_OUT0#3/PCNT1_S0IN/US2_CLK_13") (pintype "bidirectional"))
      (node (ref "SD1") (pin "5") (pinfunction "5_5") (pintype "bidirectional"))
    )
    (net (code "83") (name "PC5_SD_CS") (class "Default")
      (node (ref "IC2") (pin "14") (pinfunction "PC5/ACMP0_CH5/LETIM0_OUT1#3/PCNT1_S1IN/US2_CS_14") (pintype "bidirectional"))
      (node (ref "SD1") (pin "1") (pinfunction "1_1") (pintype "bidirectional"))
    )
    (net (code "84") (name "PC6_SD_CD") (class "Default")
      (node (ref "IC2") (pin "37") (pinfunction "PC6/ACMP0_CH6/I2C0_SDA#2/LEU1_TX#0_37") (pintype "bidirectional"))
      (node (ref "R21") (pin "1") (pinfunction "1_1") (pintype "passive"))
      (node (ref "SD1") (pin "CDS") (pinfunction "CDS_CDS") (pintype "passive"))
    )
    (net (code "85") (name "PC7_SD_WP") (class "Default")
      (node (ref "IC2") (pin "38") (pinfunction "PC7/ACMP0_CH7/I2C0_SCL#2/LEU1_RX#0_38") (pintype "bidirectional"))
      (node (ref "R23") (pin "1") (pinfunction "1_1") (pintype "passive"))
      (node (ref "SD1") (pin "WPS") (pinfunction "WPS_WPS") (pintype "passive"))
    )
    (net (code "86") (name "PC8_RFID1_MOSFET") (class "Default")
      (node (ref "IC2") (pin "41") (pinfunction "PC8/ACMP1_CH0/TIM2_CC0#2/US0_CS#2_41") (pintype "bidirectional"))
      (node (ref "R26") (pin "2") (pinfunction "2_2") (pintype "passive"))
    )
    (net (code "87") (name "PC9_RFID2_MOSFET") (class "Default")
      (node (ref "IC2") (pin "42") (pinfunction "PC9/ACMP1_CH1/TIM2_CC1#2/US0_CLK#2_42") (pintype "bidirectional"))
      (node (ref "R33") (pin "2") (pinfunction "2_2") (pintype "passive"))
    )
    (net (code "88") (name "PC10_RFID3_MOSFET") (class "Default")
      (node (ref "IC2") (pin "43") (pinfunction "PC10/ACMP1_CH2/TIM2_CC2#2/US0_RX#2_43") (pintype "bidirectional"))
      (node (ref "R38") (pin "2") (pinfunction "2_2") (pintype "passive"))
    )
    (net (code "89") (name "PC11_LINEAR_ENABLE") (class "Default")
      (node (ref "IC2") (pin "44") (pinfunction "PC11/ACMP1_CH3/US0_TX#2_44") (pintype "bidirectional"))
      (node (ref "X12") (pin "1") (pinfunction "1_1") (pintype "passive"))
    )
    (net (code "90") (name "PC12_SD_PULLUP") (class "Default")
      (node (ref "IC2") (pin "45") (pinfunction "PC12/ACMP1_CH4/CMU_CLK0#1_45") (pintype "bidirectional"))
      (node (ref "R21") (pin "2") (pinfunction "2_2") (pintype "passive"))
    )
    (net (code "91") (name "PC13_LINEAR_CLK") (class "Default")
      (node (ref "IC2") (pin "46") (pinfunction "PC13/ACMP1_CH5/PCNT0_S0IN#0/TIM0_CDTI0#1,3/TIM1_CC0#0_46") (pintype "bidirectional"))
      (node (ref "X12") (pin "3") (pinfunction "1_3") (pintype "passive"))
    )
    (net (code "92") (name "PC14_LINEAR_I_AB") (class "Default")
      (node (ref "IC2") (pin "47") (pinfunction "PC14/ACMP1_CH6/PCNT0_S1IN#0/TIM0_CDTI1#1,3/TIM1_CC1#0_47") (pintype "bidirectional"))
      (node (ref "X12") (pin "4") (pinfunction "1_4") (pintype "passive"))
    )
    (net (code "93") (name "PC15_LA_MOSFET") (class "Default")
      (node (ref "IC2") (pin "48") (pinfunction "PC15/ACMP1_CH7/DBG_SWO#1/TIM0_CDTI2#1,3/TIM1_CC2#0_48") (pintype "bidirectional"))
      (node (ref "R62") (pin "2") (pinfunction "2_2") (pintype "passive"))
    )
    (net (code "94") (name "PD0_SD_POWER") (class "Default")
      (node (ref "IC2") (pin "28") (pinfunction "PD0/ADC0_CH0/PCNT2_S0IN#0/US1_TX#1_28") (pintype "bidirectional"))
      (node (ref "R12") (pin "2") (pinfunction "2_2") (pintype "passive"))
    )
    (net (code "95") (name "PD1_DCF77_ENABLE") (class "Default")
      (node (ref "IC2") (pin "29") (pinfunction "PD1/ADC0_CH1/PCNT2_S1IN#0/TIM0_CC0#3/US1_RX#1_29") (pintype "bidirectional"))
      (node (ref "X6") (pin "2") (pinfunction "1_2") (pintype "passive"))
    )
    (net (code "96") (name "PD2_DCF77_SIGNAL") (class "Default")
      (node (ref "IC2") (pin "30") (pinfunction "PD2/ADC0_CH2/TIM0_CC1#3/US1_CLK#1_30") (pintype "bidirectional"))
      (node (ref "X6") (pin "1") (pinfunction "1_1") (pintype "passive"))
    )
    (net (code "97") (name "PD3_N_SCHALTER_AUF") (class "Default")
      (node (ref "IC2") (pin "31") (pinfunction "PD3/ADC0_CH3/TIM0_CC2#3/US1_CS#1_31") (pintype "bidirectional"))
      (node (ref "X13") (pin "1") (pinfunction "1_1") (pintype "passive"))
    )
    (net (code "98") (name "PD4_LEUART_TX") (class "Default")
      (node (ref "IC2") (pin "32") (pinfunction "PD4/ADC0_CH4/LEU0_TX#0_32") (pintype "bidirectional"))
      (node (ref "R25") (pin "1") (pinfunction "1_1") (pintype "passive"))
    )
    (net (code "99") (name "PD5_LEUART_RX") (class "Default")
      (node (ref "IC2") (pin "33") (pinfunction "PD5/ADC0_CH5/LEU0_RX#0_33") (pintype "bidirectional"))
      (node (ref "R24") (pin "1") (pinfunction "1_1") (pintype "passive"))
    )
    (net (code "100") (name "PD6_PIR1_SIGNAL") (class "Default")
      (node (ref "IC2") (pin "34") (pinfunction "PD6/ADC0_CH6/I2C0_SDA#1/LETIM0_OUT0#0_34") (pintype "bidirectional"))
      (node (ref "X3") (pin "1.5") (pinfunction "1_1.5") (pintype "passive"))
    )
    (net (code "101") (name "PD7_PIR2_SIGNAL") (class "Default")
      (node (ref "IC2") (pin "35") (pinfunction "PD7/ADC0_CH7/I2C0_SCL#1/LETIM0_OUT1#0_35") (pintype "bidirectional"))
      (node (ref "X3") (pin "1.6") (pinfunction "1_1.6") (pintype "passive"))
    )
    (net (code "102") (name "PE8_SERVOPL_MOSFET") (class "Default")
      (node (ref "IC2") (pin "56") (pinfunction "PE8/PCNT2_S0IN#1_56") (pintype "bidirectional"))
      (node (ref "R61") (pin "2") (pinfunction "2_2") (pintype "passive"))
    )
    (net (code "103") (name "PE9_SERVO_AUF") (class "Default")
      (node (ref "IC2") (pin "57") (pinfunction "PE9/PCNT2_S1IN#1_57") (pintype "bidirectional"))
      (node (ref "X11") (pin "1") (pinfunction "1_1") (pintype "passive"))
    )
    (net (code "104") (name "PE10_SERVO_ZU") (class "Default")
      (node (ref "IC2") (pin "58") (pinfunction "PE10/TIM1_CC0#1/US0_TX#0_58") (pintype "bidirectional"))
      (node (ref "X11") (pin "2") (pinfunction "1_2") (pintype "passive"))
    )
    (net (code "105") (name "PE11_N_SCHALTER_AUF") (class "Default")
      (node (ref "IC2") (pin "59") (pinfunction "PE11/TIM1_CC1#1/US0_RX#0_59") (pintype "bidirectional"))
      (node (ref "X11") (pin "3") (pinfunction "1_3") (pintype "passive"))
    )
    (net (code "106") (name "PE12_N_SCHALTER_ZU") (class "Default")
      (node (ref "IC2") (pin "60") (pinfunction "PE12/TIM1_CC2#1/US0_CLK#0_60") (pintype "bidirectional"))
      (node (ref "X11") (pin "4") (pinfunction "1_4") (pintype "passive"))
    )
    (net (code "107") (name "PE13_LB1_SIGNAL") (class "Default")
      (node (ref "IC2") (pin "61") (pinfunction "PE13/ACMP0_O/US0_CS#0_61") (pintype "bidirectional"))
      (node (ref "X4") (pin "3") (pinfunction "1_3") (pintype "passive"))
    )
    (net (code "108") (name "PE14_LB2_SIGNAL") (class "Default")
      (node (ref "IC2") (pin "62") (pinfunction "PE14/LEU0_TX#2_62") (pintype "bidirectional"))
      (node (ref "X4") (pin "4") (pinfunction "1_4") (pintype "passive"))
    )
    (net (code "109") (name "PE15_LINEAR_DIR") (class "Default")
      (node (ref "IC2") (pin "63") (pinfunction "PE15/LEU0_RX#2_63") (pintype "bidirectional"))
      (node (ref "X12") (pin "2") (pinfunction "1_2") (pintype "passive"))
    )
    (net (code "110") (name "PF0_DBG_SWCLK") (class "Default")
      (node (ref "IC2") (pin "49") (pinfunction "PF0/DBG_SWCLK#0,1/LETIM0_OUT0#2_49") (pintype "bidirectional"))
      (node (ref "X2") (pin "4") (pinfunction "4_4") (pintype "passive"))
    )
    (net (code "111") (name "PF1_DBG_SWDIO") (class "Default")
      (node (ref "IC2") (pin "50") (pinfunction "PF1/DBG_SWDIO#0,1/LETIM0_OUT1#2_50") (pintype "bidirectional"))
      (node (ref "X2") (pin "2") (pinfunction "2_2") (pintype "passive"))
    )
    (net (code "112") (name "PF2_DBG_SWO") (class "Default")
      (node (ref "IC2") (pin "51") (pinfunction "PF2/ACMP1_O/DBG_SWO#0_51") (pintype "bidirectional"))
      (node (ref "X2") (pin "6") (pinfunction "6_6") (pintype "passive"))
    )
    (net (code "113") (name "RFID_GND_LB") (class "Default")
      (node (ref "T5") (pin "1") (pinfunction "D_1") (pintype "passive"))
      (node (ref "X4") (pin "5") (pinfunction "1_5") (pintype "passive"))
    )
    (net (code "114") (name "RXD_HOST") (class "Default")
      (node (ref "J1") (pin "P$3") (pinfunction "3-RIGHT_P$3") (pintype "bidirectional"))
      (node (ref "R25") (pin "2") (pinfunction "2_2") (pintype "passive"))
    )
    (net (code "115") (name "SD_+3.3V") (class "Default")
      (node (ref "C28") (pin "1") (pinfunction "1_1") (pintype "passive"))
      (node (ref "C29") (pin "1") (pinfunction "1_1") (pintype "passive"))
      (node (ref "R18") (pin "2") (pinfunction "2_2") (pintype "passive"))
      (node (ref "R19") (pin "2") (pinfunction "2_2") (pintype "passive"))
      (node (ref "R20") (pin "2") (pinfunction "2_2") (pintype "passive"))
      (node (ref "R22") (pin "2") (pinfunction "2_2") (pintype "passive"))
      (node (ref "R23") (pin "2") (pinfunction "2_2") (pintype "passive"))
      (node (ref "SD1") (pin "4") (pinfunction "4_4") (pintype "bidirectional"))
      (node (ref "T2") (pin "1") (pinfunction "D_1") (pintype "passive"))
    )
    (net (code "116") (name "TXD_HOST") (class "Default")
      (node (ref "J1") (pin "P$2") (pinfunction "2-LEFT_P$2") (pintype "bidirectional"))
      (node (ref "R24") (pin "2") (pinfunction "2_2") (pintype "passive"))
    )
    (net (code "117") (name "UA1") (class "Default")
      (node (ref "C49") (pin "1") (pinfunction "1_1") (pintype "passive"))
      (node (ref "C51") (pin "1") (pinfunction "1_1") (pintype "passive"))
      (node (ref "C53") (pin "1") (pinfunction "1_1") (pintype "passive"))
      (node (ref "F1") (pin "P$1") (pinfunction "1_P$1") (pintype "passive"))
      (node (ref "L3") (pin "2") (pinfunction "2_2") (pintype "passive"))
      (node (ref "LSP1") (pin "MP") (pinfunction "MP_MP") (pintype "passive"))
      (node (ref "R53") (pin "2") (pinfunction "2_2") (pintype "passive"))
      (node (ref "R59") (pin "2") (pinfunction "2_2") (pintype "passive"))
    )
    (net (code "118") (name "UA2") (class "Default")
      (node (ref "C50") (pin "1") (pinfunction "1_1") (pintype "passive"))
      (node (ref "C52") (pin "1") (pinfunction "1_1") (pintype "passive"))
      (node (ref "C54") (pin "1") (pinfunction "1_1") (pintype "passive"))
      (node (ref "F2") (pin "P$1") (pinfunction "1_P$1") (pintype "passive"))
      (node (ref "L4") (pin "2") (pinfunction "2_2") (pintype "passive"))
      (node (ref "LSP2") (pin "MP") (pinfunction "MP_MP") (pintype "passive"))
      (node (ref "R56") (pin "2") (pinfunction "2_2") (pintype "passive"))
      (node (ref "R60") (pin "2") (pinfunction "2_2") (pintype "passive"))
    )
    (net (code "119") (name "VDCF") (class "Default")
      (node (ref "C6") (pin "+") (pinfunction "+_+") (pintype "passive"))
      (node (ref "C8") (pin "1") (pinfunction "1_1") (pintype "passive"))
      (node (ref "D1") (pin "1") (pinfunction "C_1") (pintype "passive"))
      (node (ref "X6") (pin "4") (pinfunction "1_4") (pintype "passive"))
    )
    (net (code "120") (name "VDD_5V_CAM1") (class "Default")
      (node (ref "F1") (pin "P$2") (pinfunction "2_P$2") (pintype "passive"))
      (node (ref "X10") (pin "1") (pinfunction "1_1") (pintype "passive"))
    )
    (net (code "121") (name "VDD_5V_CAM2") (class "Default")
      (node (ref "F2") (pin "P$2") (pinfunction "2_P$2") (pintype "passive"))
      (node (ref "X10") (pin "3") (pinfunction "1_3") (pintype "passive"))
    )
    (net (code "122") (name "VDD_LINEAR") (class "Default")
      (node (ref "C56") (pin "1") (pinfunction "1_1") (pintype "passive"))
      (node (ref "F6") (pin "P$1") (pinfunction "1_P$1") (pintype "passive"))
      (node (ref "R70") (pin "2") (pinfunction "2_2") (pintype "passive"))
      (node (ref "T13") (pin "1") (pinfunction "D_1") (pintype "passive"))
    )
    (net (code "123") (name "VDD_LINEAR_12V") (class "Default")
      (node (ref "F6") (pin "P$2") (pinfunction "2_P$2") (pintype "passive"))
      (node (ref "X15") (pin "1") (pinfunction "1_1") (pintype "passive"))
    )
    (net (code "124") (name "VDD_RFID1") (class "Default")
      (node (ref "C30") (pin "1") (pinfunction "1_1") (pintype "passive"))
      (node (ref "R32") (pin "2") (pinfunction "2_2") (pintype "passive"))
      (node (ref "T4") (pin "1") (pinfunction "D_1") (pintype "passive"))
      (node (ref "X8") (pin "3") (pinfunction "1_3") (pintype "passive"))
    )
    (net (code "125") (name "VDD_RFID2") (class "Default")
      (node (ref "C31") (pin "1") (pinfunction "1_1") (pintype "passive"))
      (node (ref "R37") (pin "2") (pinfunction "2_2") (pintype "passive"))
      (node (ref "T7") (pin "1") (pinfunction "D_1") (pintype "passive"))
      (node (ref "X8") (pin "5") (pinfunction "1_5") (pintype "passive"))
    )
    (net (code "126") (name "VDD_RFID3") (class "Default")
      (node (ref "C32") (pin "1") (pinfunction "1_1") (pintype "passive"))
      (node (ref "R42") (pin "2") (pinfunction "2_2") (pintype "passive"))
      (node (ref "T9") (pin "1") (pinfunction "D_1") (pintype "passive"))
      (node (ref "X8") (pin "7") (pinfunction "1_7") (pintype "passive"))
    )
    (net (code "127") (name "VDD_SERVO") (class "Default")
      (node (ref "C55") (pin "1") (pinfunction "1_1") (pintype "passive"))
      (node (ref "F5") (pin "P$1") (pinfunction "1_P$1") (pintype "passive"))
      (node (ref "R69") (pin "2") (pinfunction "2_2") (pintype "passive"))
      (node (ref "T12") (pin "1") (pinfunction "D_1") (pintype "passive"))
    )
    (net (code "128") (name "VDD_SERVO_12V") (class "Default")
      (node (ref "F5") (pin "P$2") (pinfunction "2_P$2") (pintype "passive"))
      (node (ref "X14") (pin "1") (pinfunction "1_1") (pintype "passive"))
    )
    (net (code "129") (name "VFRONT") (class "Default")
      (node (ref "C7") (pin "+") (pinfunction "+_+") (pintype "passive"))
      (node (ref "C9") (pin "1") (pinfunction "1_1") (pintype "passive"))
      (node (ref "D2") (pin "1") (pinfunction "C_1") (pintype "passive"))
      (node (ref "X4") (pin "1") (pinfunction "1_1") (pintype "passive"))
    )
    (net (code "130") (name "VMCU") (class "Default")
      (node (ref "C11") (pin "2") (pinfunction "2_2") (pintype "passive"))
      (node (ref "C16") (pin "2") (pinfunction "2_2") (pintype "passive"))
      (node (ref "C17") (pin "2") (pinfunction "2_2") (pintype "passive"))
      (node (ref "C18") (pin "2") (pinfunction "2_2") (pintype "passive"))
      (node (ref "C22") (pin "2") (pinfunction "2_2") (pintype "passive"))
      (node (ref "C24") (pin "2") (pinfunction "2_2") (pintype "passive"))
      (node (ref "C26") (pin "2") (pinfunction "2_2") (pintype "passive"))
      (node (ref "C27") (pin "2") (pinfunction "2_2") (pintype "passive"))
      (node (ref "D4") (pin "1") (pinfunction "C_1") (pintype "passive"))
      (node (ref "IC2") (pin "26") (pinfunction "IOVDD_3_26") (pintype "power_in"))
      (node (ref "IC2") (pin "39") (pinfunction "VDD_DREG_39") (pintype "power_in"))
      (node (ref "IC2") (pin "55") (pinfunction "IOVDD_5_55") (pintype "power_in"))
      (node (ref "IC2") (pin "8") (pinfunction "IOVDD_0_8") (pintype "power_in"))
      (node (ref "L2") (pin "1") (pinfunction "1_1") (pintype "passive"))
      (node (ref "R10") (pin "1") (pinfunction "1_1") (pintype "passive"))
      (node (ref "R15") (pin "2") (pinfunction "2_2") (pintype "passive"))
      (node (ref "R17") (pin "2") (pinfunction "2_2") (pintype "passive"))
      (node (ref "R28") (pin "2") (pinfunction "2_2") (pintype "passive"))
      (node (ref "R34") (pin "2") (pinfunction "2_2") (pintype "passive"))
      (node (ref "R39") (pin "2") (pinfunction "2_2") (pintype "passive"))
      (node (ref "R74") (pin "2") (pinfunction "2_2") (pintype "passive"))
      (node (ref "T4") (pin "2") (pinfunction "S_2") (pintype "passive"))
      (node (ref "T7") (pin "2") (pinfunction "S_2") (pintype "passive"))
      (node (ref "T9") (pin "2") (pinfunction "S_2") (pintype "passive"))
      (node (ref "X2") (pin "1") (pinfunction "1_1") (pintype "passive"))
      (node (ref "X3") (pin "1.1") (pinfunction "1_1.1") (pintype "passive"))
      (node (ref "X3") (pin "1.2") (pinfunction "1_1.2") (pintype "passive"))
      (node (ref "X8") (pin "1") (pinfunction "1_1") (pintype "passive"))
    )
    (net (code "131") (name "VSD") (class "Default")
      (node (ref "C10") (pin "1") (pinfunction "1_1") (pintype "passive"))
      (node (ref "C5") (pin "+") (pinfunction "+_+") (pintype "passive"))
      (node (ref "D3") (pin "1") (pinfunction "C_1") (pintype "passive"))
      (node (ref "R13") (pin "2") (pinfunction "2_2") (pintype "passive"))
      (node (ref "T2") (pin "2") (pinfunction "S_2") (pintype "passive"))
    )
    (net (code "132") (name "_") (class "Default")
      (node (ref "Q1") (pin "10") (pinfunction "D_10") (pintype "passive"))
      (node (ref "Q1") (pin "11") (pinfunction "D_11") (pintype "passive"))
      (node (ref "Q1") (pin "5") (pinfunction "D_5") (pintype "passive"))
      (node (ref "Q1") (pin "6") (pinfunction "D_6") (pintype "passive"))
      (node (ref "Q1") (pin "7") (pinfunction "D_7") (pintype "passive"))
      (node (ref "Q1") (pin "8") (pinfunction "D_8") (pintype "passive"))
      (node (ref "Q1") (pin "9") (pinfunction "D_9") (pintype "passive"))
      (node (ref "X1") (pin "2") (pinfunction "1_2") (pintype "passive"))
    )
    (net (code "133") (name "unconnected-(IC2D-PD8{slash}CMU_CLK1#1-Pad36)") (class "Default")
      (node (ref "IC2") (pin "36") (pinfunction "PD8/CMU_CLK1#1_36") (pintype "bidirectional"))
    )
    (net (code "134") (name "unconnected-(IC2F-PF3{slash}TIM0_CDTI0#2-Pad52)") (class "Default")
      (node (ref "IC2") (pin "52") (pinfunction "PF3/TIM0_CDTI0#2_52") (pintype "bidirectional"))
    )
    (net (code "135") (name "unconnected-(IC2F-PF4{slash}TIM0_CDTI1#2-Pad53)") (class "Default")
      (node (ref "IC2") (pin "53") (pinfunction "PF4/TIM0_CDTI1#2_53") (pintype "bidirectional"))
    )
    (net (code "136") (name "unconnected-(IC2F-PF5{slash}TIM0_CDTI2#2-Pad54)") (class "Default")
      (node (ref "IC2") (pin "54") (pinfunction "PF5/TIM0_CDTI2#2_54") (pintype "bidirectional"))
    )
    (net (code "137") (name "unconnected-(IC3-PWGD-Pad6)") (class "Default")
      (node (ref "IC3") (pin "6") (pinfunction "PWGD_6") (pintype "output"))
    )
    (net (code "138") (name "unconnected-(IC4-PWGD-Pad6)") (class "Default")
      (node (ref "IC4") (pin "6") (pinfunction "PWGD_6") (pintype "output"))
    )
    (net (code "139") (name "unconnected-(SD1-PadG1)") (class "Default")
      (node (ref "SD1") (pin "G1") (pinfunction "G1_G1") (pintype "passive"))
    )
    (net (code "140") (name "unconnected-(SD1-PadG2)") (class "Default")
      (node (ref "SD1") (pin "G2") (pinfunction "G2_G2") (pintype "passive"))
    )
    (net (code "141") (name "unconnected-(SD1-PadG3)") (class "Default")
      (node (ref "SD1") (pin "G3") (pinfunction "G3_G3") (pintype "passive"))
    )
    (net (code "142") (name "unconnected-(SD1-PadG4)") (class "Default")
      (node (ref "SD1") (pin "G4") (pinfunction "G4_G4") (pintype "passive"))
    )
    (net (code "143") (name "unconnected-(X2-Pad7)") (class "Default")
      (node (ref "X2") (pin "7") (pinfunction "7_7") (pintype "passive"))
    )
  )
)
